# PDUv1.net
KiCad netlist of a schematic drawn in EAGLE
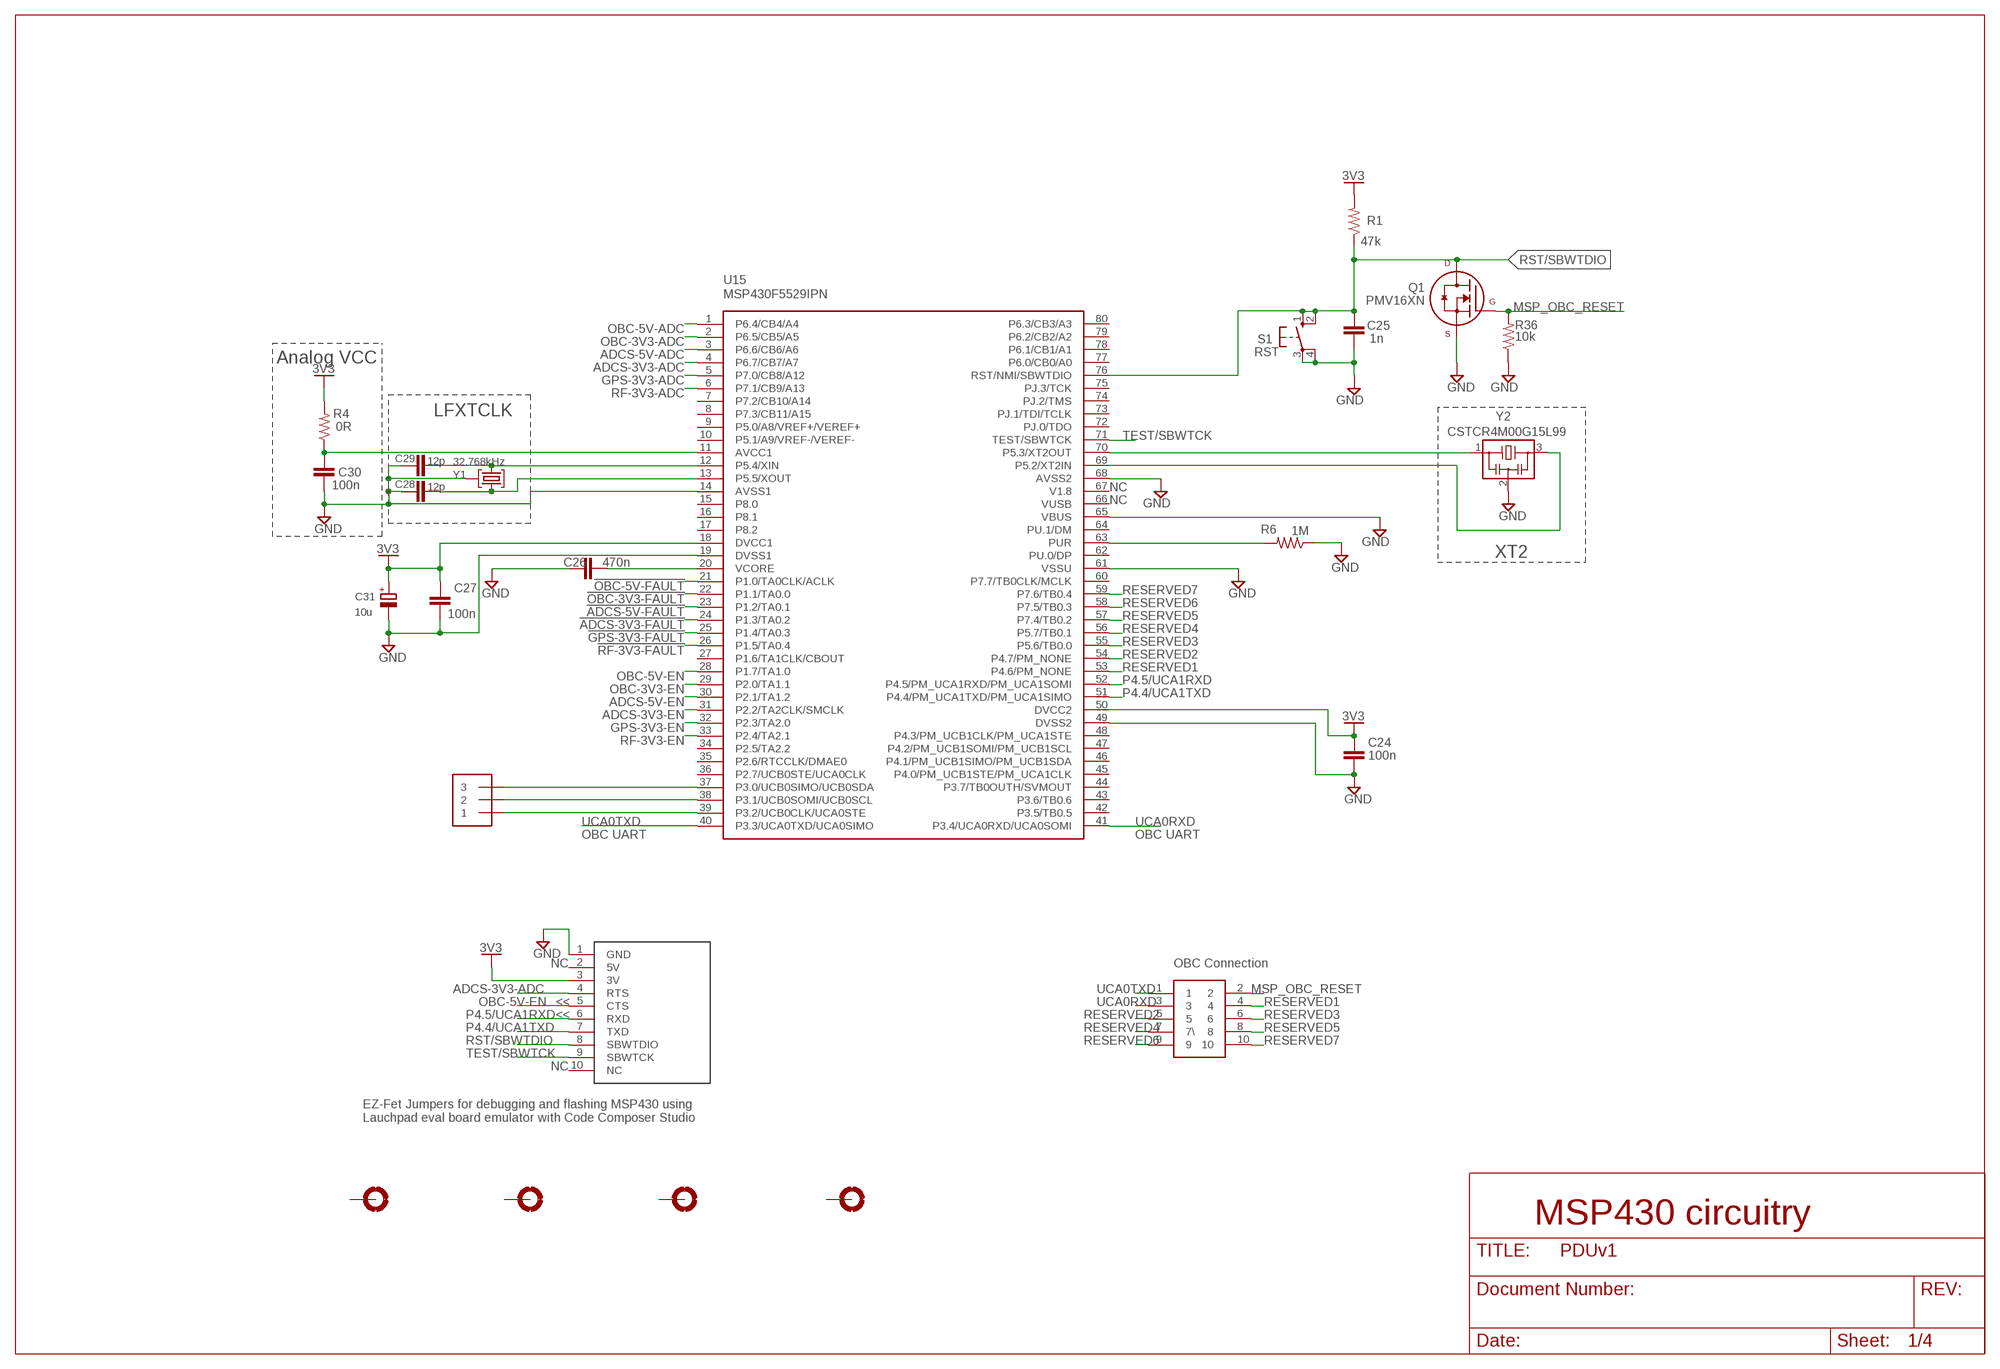
[diagram p0: schematic, sheet 1]
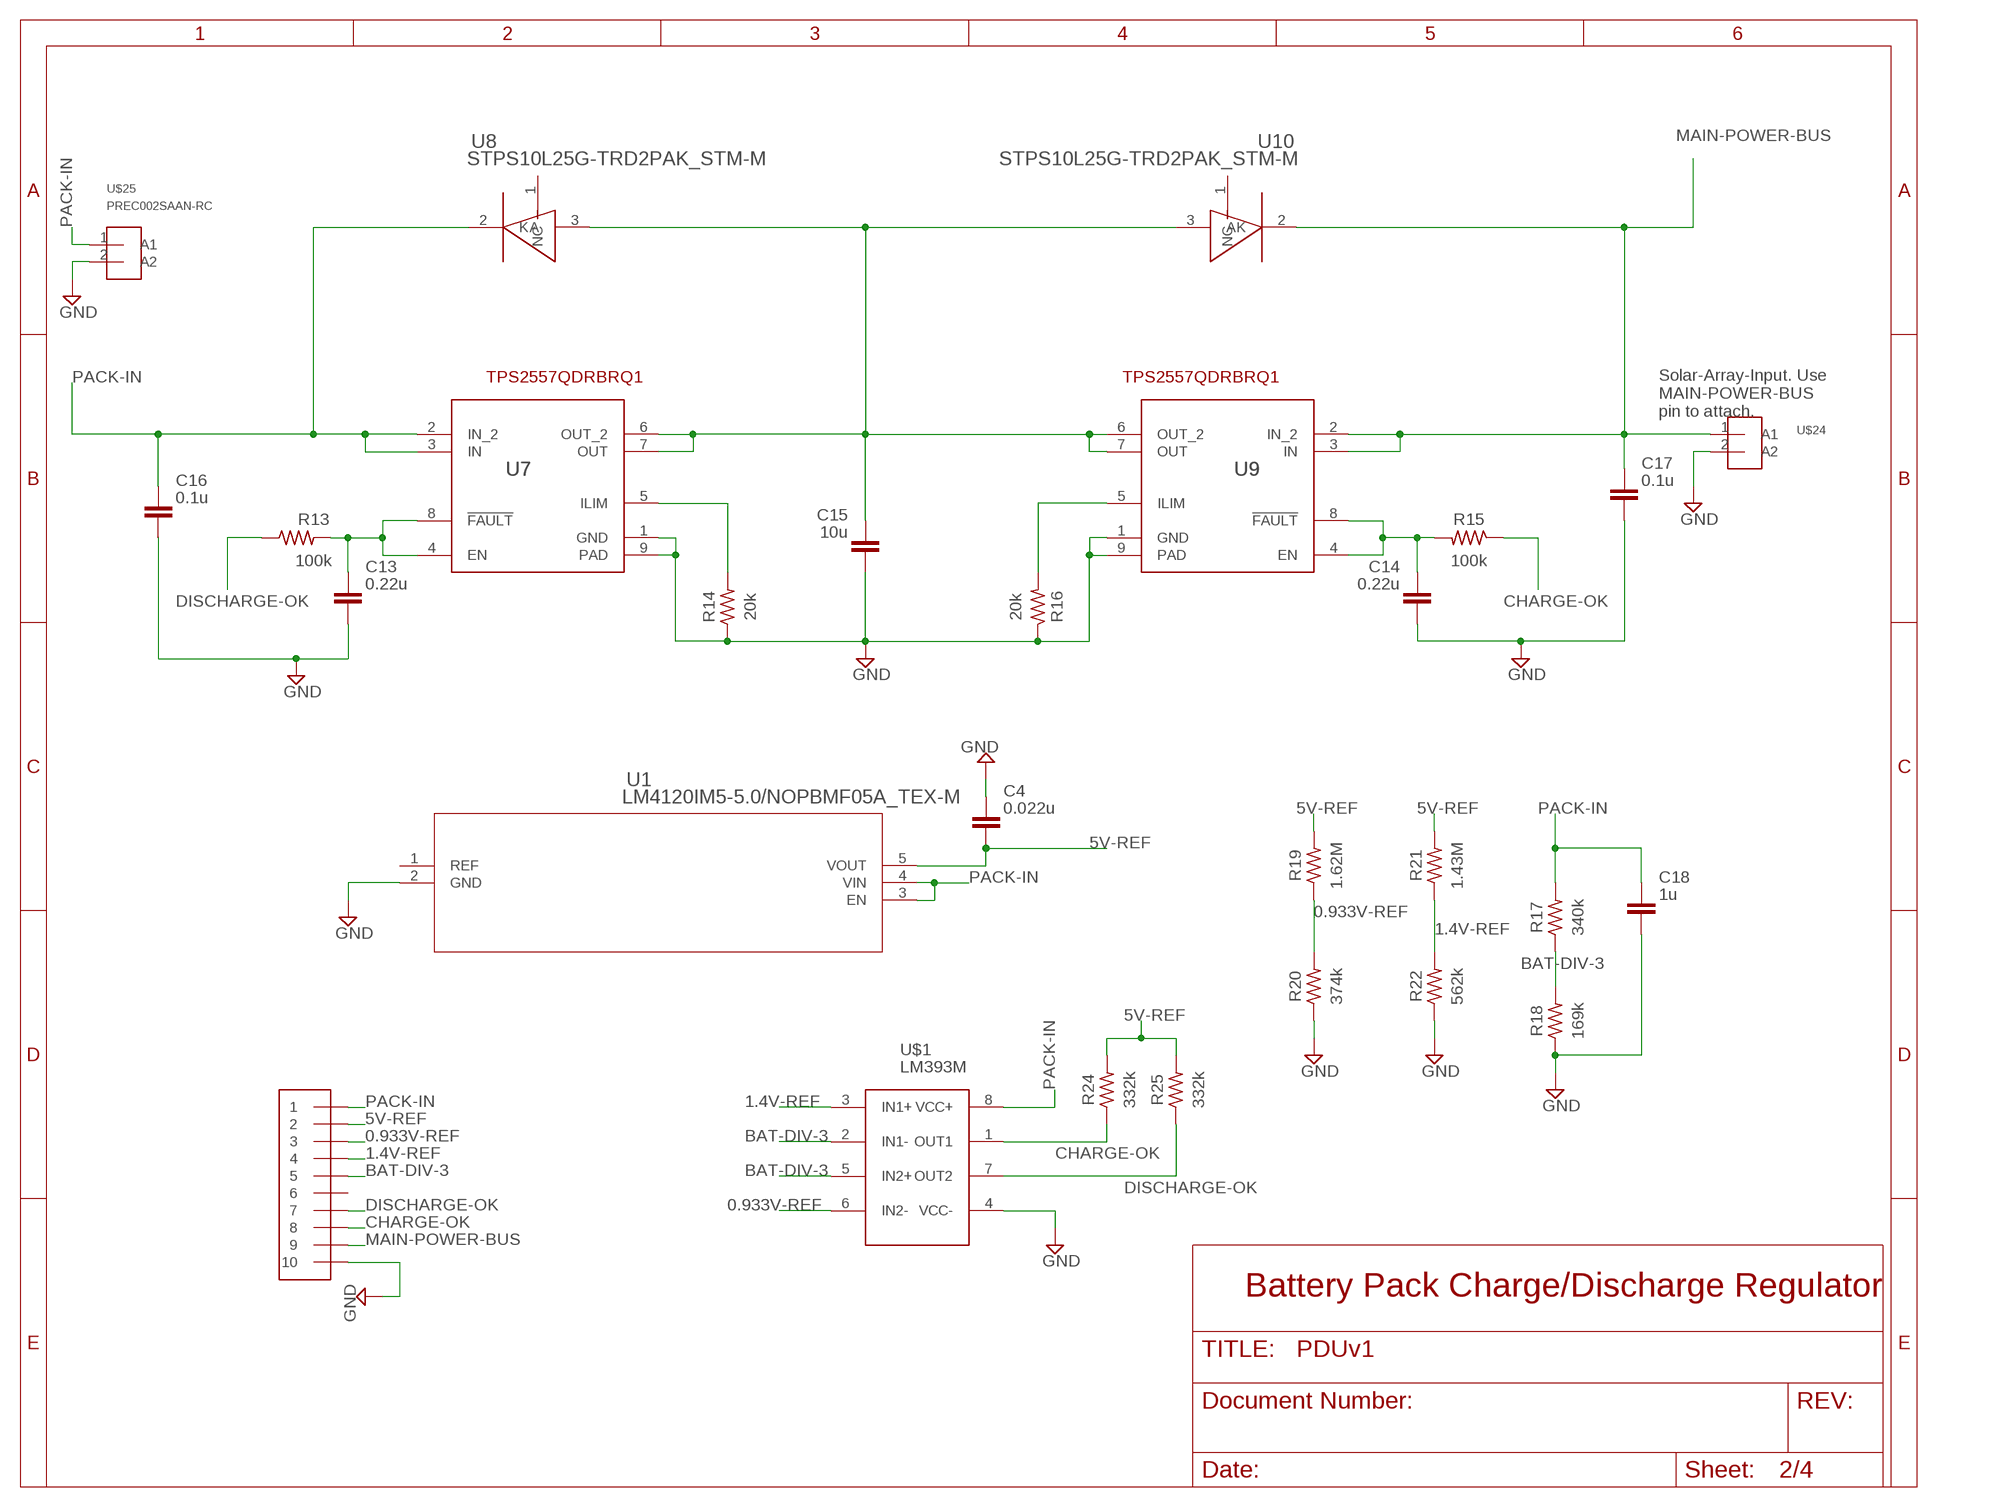
[diagram p1: schematic, sheet 2]
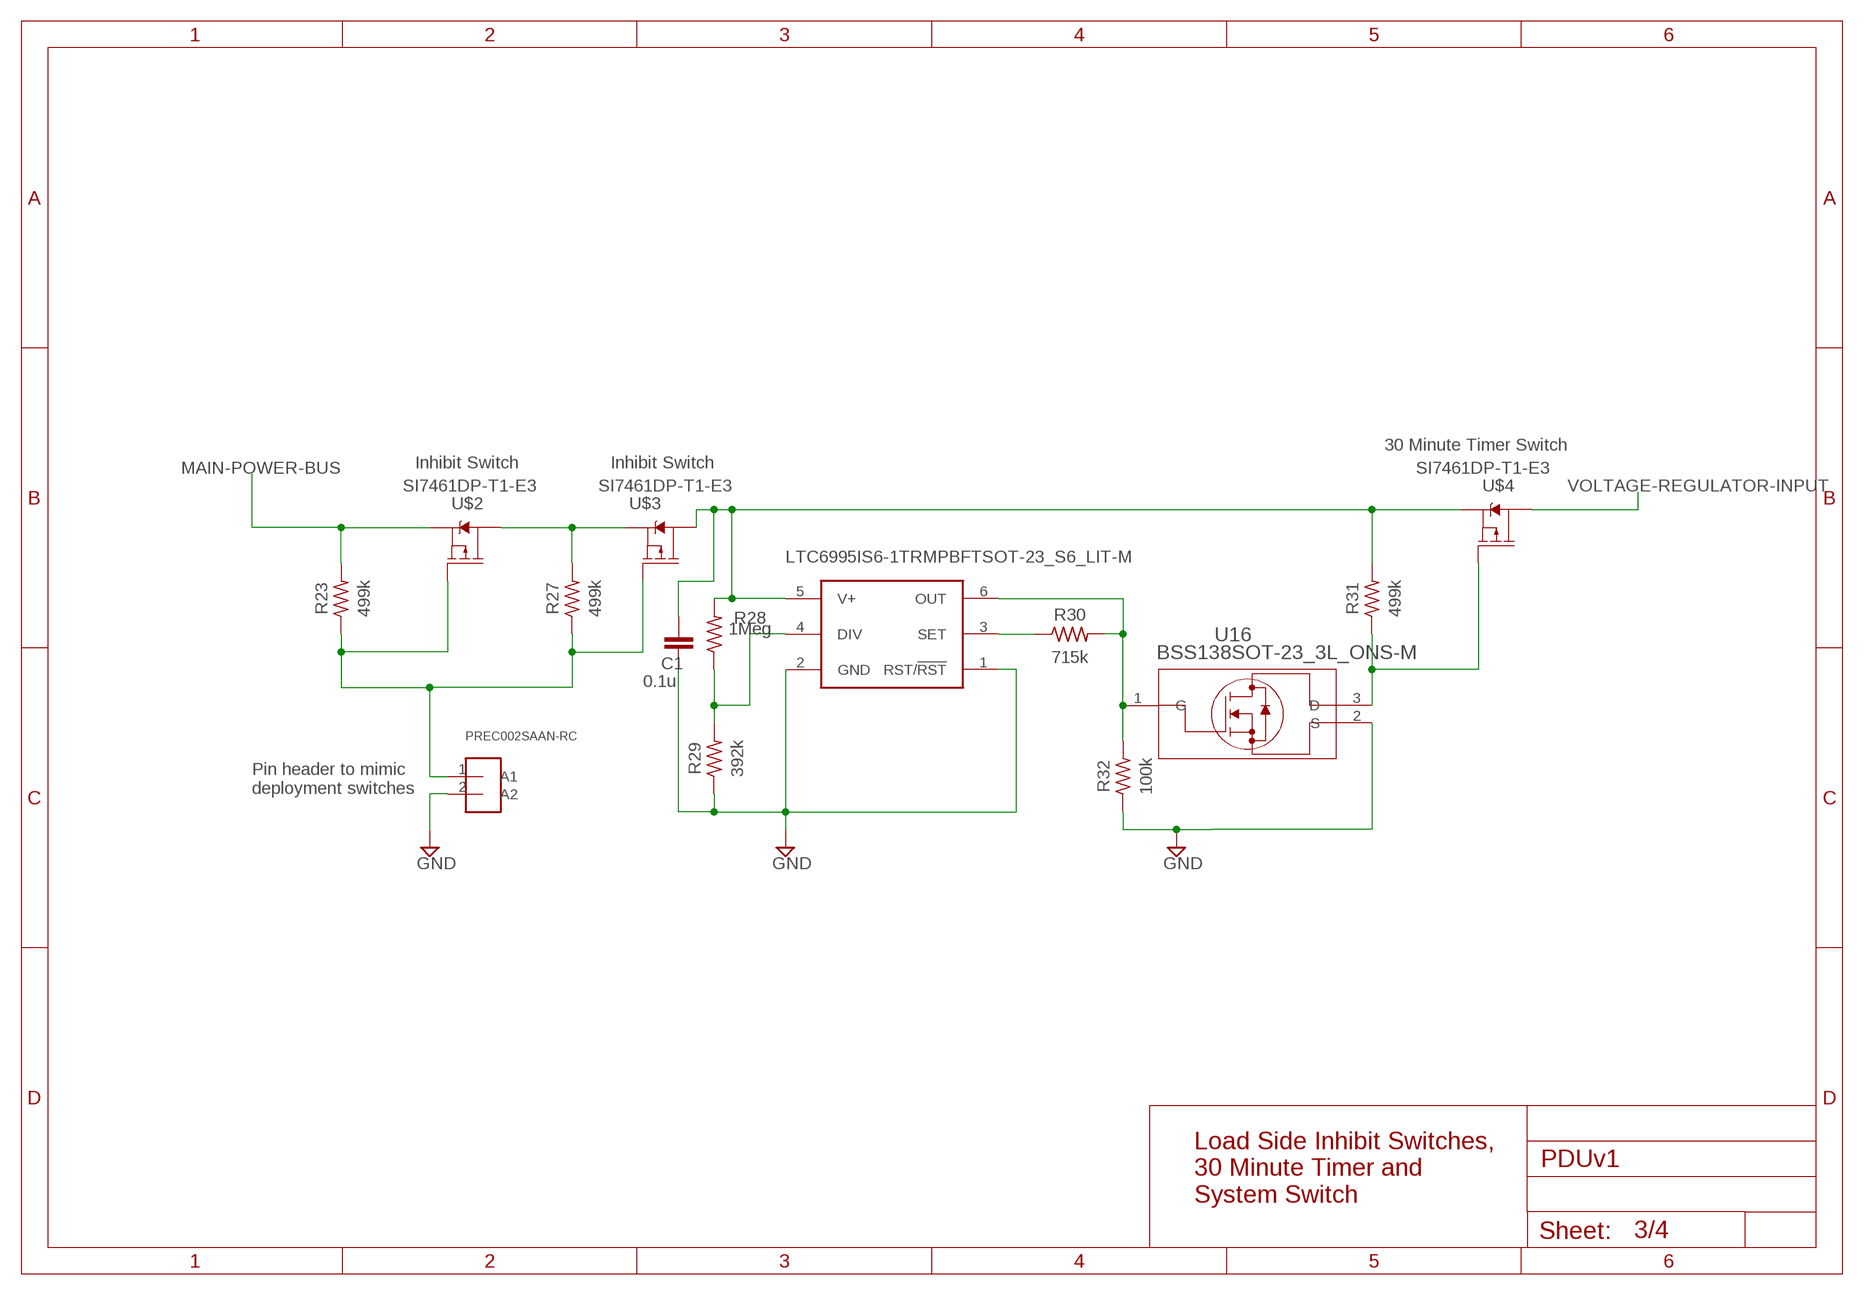
[diagram p2: schematic, sheet 3]
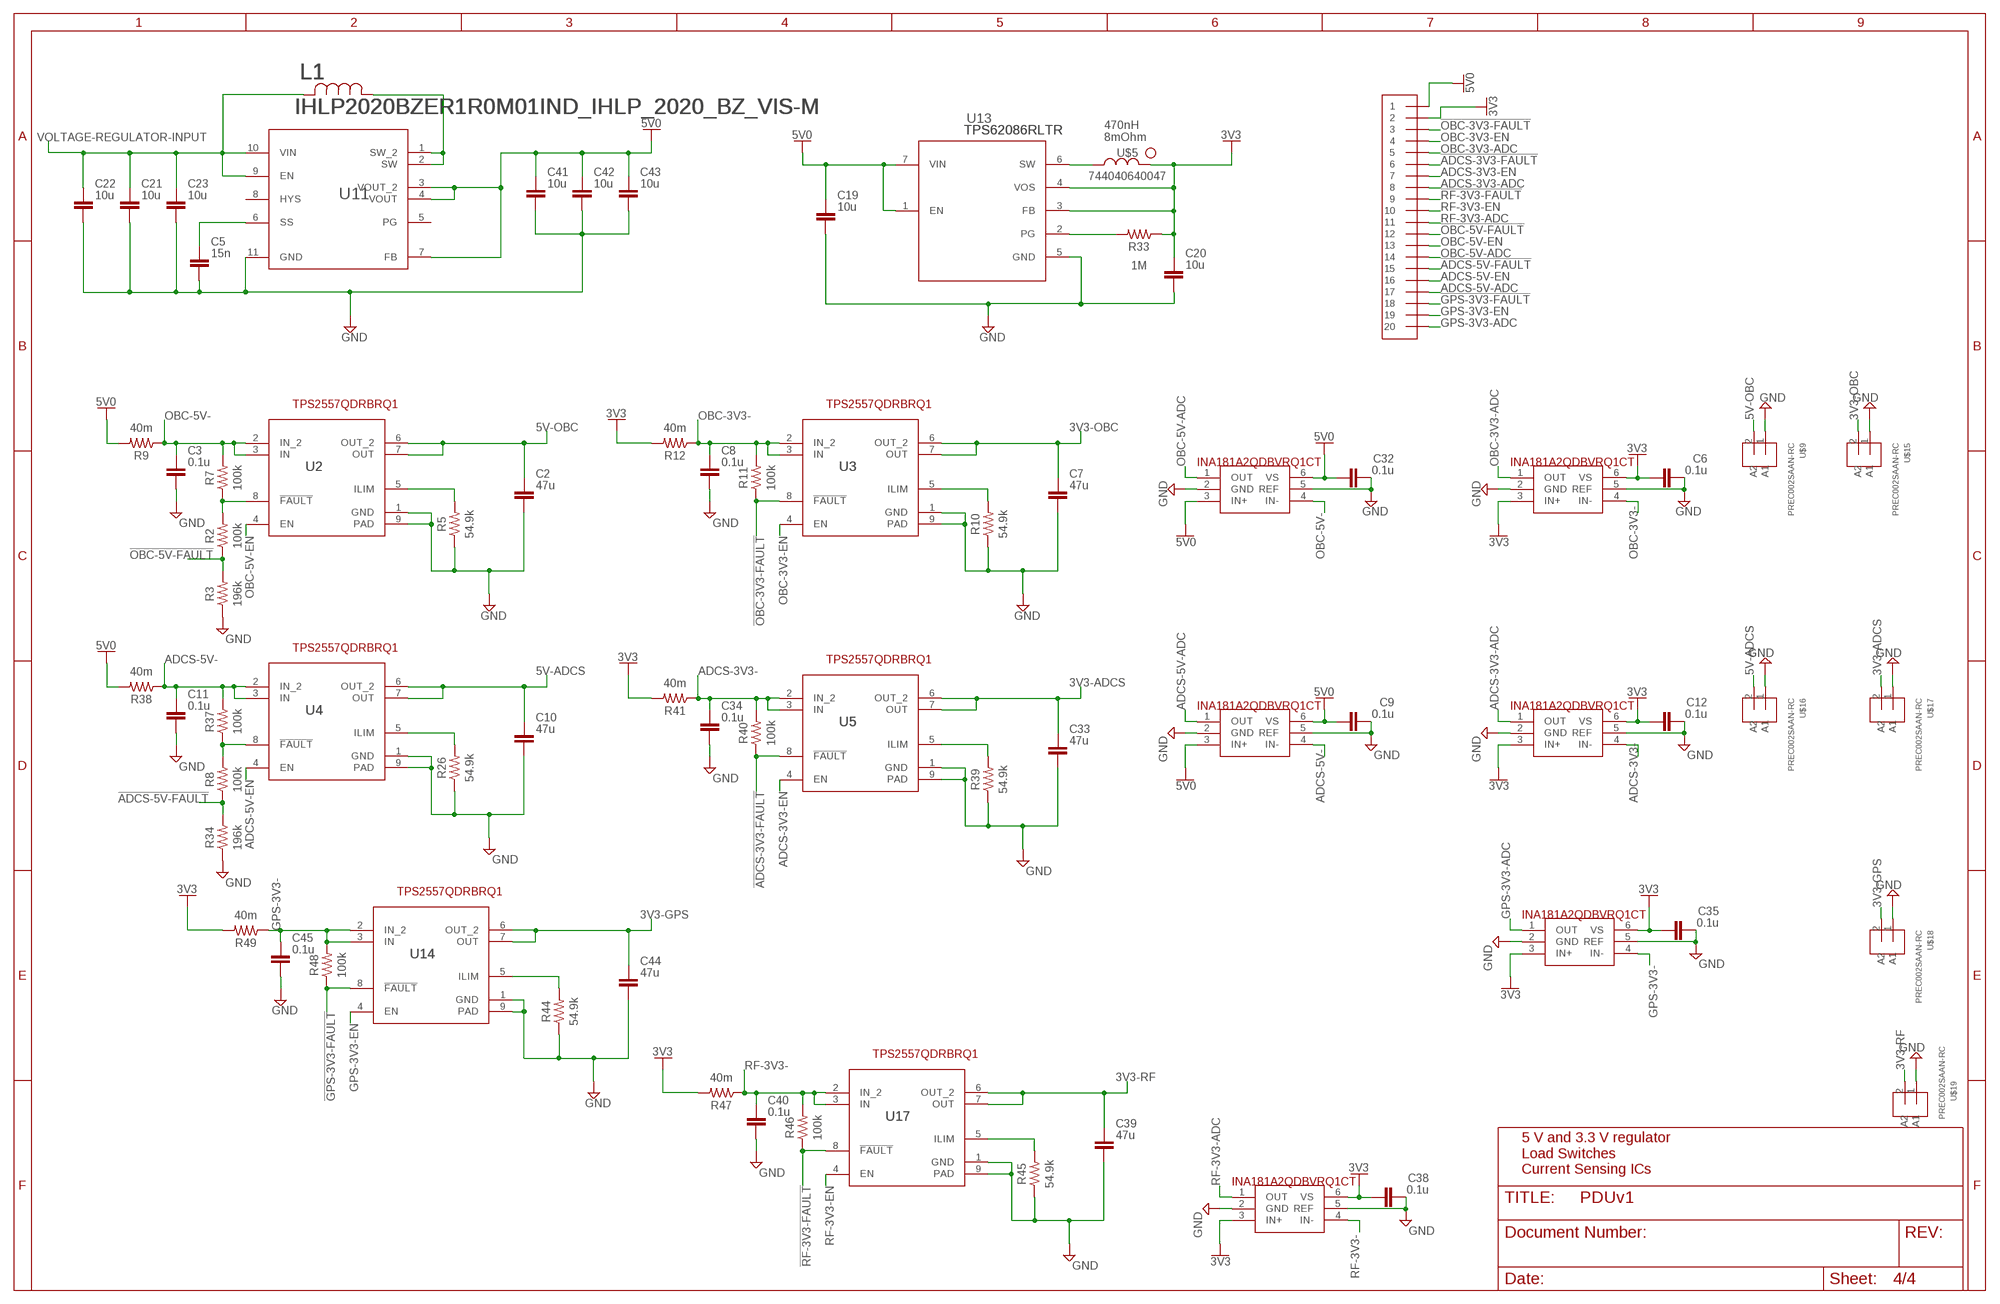
[diagram p3: schematic, sheet 4]

(export (version "E")
  (design (tool "Eeschema 10.0.6"))
  (components
    (comp (ref "C4")
      (value "0.022u")
      (footprint "eagle-import:CAPC1608X85")
      (libsource (lib "eagle-import") (part "CCHIP-0603(1608-METRIC)_"))
    )
    (comp (ref "C13")
      (value "0.22u")
      (footprint "eagle-import:CAPC1608X85")
      (libsource (lib "eagle-import") (part "CCHIP-0603(1608-METRIC)_"))
    )
    (comp (ref "C14")
      (value "0.22u")
      (footprint "eagle-import:CAPC1608X85")
      (libsource (lib "eagle-import") (part "CCHIP-0603(1608-METRIC)_"))
    )
    (comp (ref "C15")
      (value "10u")
      (footprint "eagle-import:CAPC1608X85")
      (libsource (lib "eagle-import") (part "CCHIP-0603(1608-METRIC)_"))
    )
    (comp (ref "C16")
      (value "0.1u")
      (footprint "eagle-import:CAPC1608X85")
      (libsource (lib "eagle-import") (part "CCHIP-0603(1608-METRIC)_"))
    )
    (comp (ref "C17")
      (value "0.1u")
      (footprint "eagle-import:CAPC1608X85")
      (libsource (lib "eagle-import") (part "CCHIP-0603(1608-METRIC)_"))
    )
    (comp (ref "C18")
      (value "1u")
      (footprint "eagle-import:CAPC1608X85")
      (libsource (lib "eagle-import") (part "CCHIP-0603(1608-METRIC)_"))
    )
    (comp (ref "R13")
      (value "100k")
      (footprint "eagle-import:RESC1608X60")
      (libsource (lib "eagle-import") (part "R-USCHIP-0603(1608-METRIC)_"))
    )
    (comp (ref "R14")
      (value "20k")
      (footprint "eagle-import:RESC1608X60")
      (libsource (lib "eagle-import") (part "R-USCHIP-0603(1608-METRIC)_"))
    )
    (comp (ref "R15")
      (value "100k")
      (footprint "eagle-import:RESC1608X60")
      (libsource (lib "eagle-import") (part "R-USCHIP-0603(1608-METRIC)_"))
    )
    (comp (ref "R16")
      (value "20k")
      (footprint "eagle-import:RESC1608X60")
      (libsource (lib "eagle-import") (part "R-USCHIP-0603(1608-METRIC)_"))
    )
    (comp (ref "R17")
      (value "340k")
      (footprint "eagle-import:RESC1608X60")
      (libsource (lib "eagle-import") (part "R-USCHIP-0603(1608-METRIC)_"))
    )
    (comp (ref "R18")
      (value "169k")
      (footprint "eagle-import:RESC1608X60")
      (libsource (lib "eagle-import") (part "R-USCHIP-0603(1608-METRIC)_"))
    )
    (comp (ref "R19")
      (value "1.62M")
      (footprint "eagle-import:RESC1608X60")
      (libsource (lib "eagle-import") (part "R-USCHIP-0603(1608-METRIC)_"))
    )
    (comp (ref "R20")
      (value "374k")
      (footprint "eagle-import:RESC1608X60")
      (libsource (lib "eagle-import") (part "R-USCHIP-0603(1608-METRIC)_"))
    )
    (comp (ref "R21")
      (value "1.43M")
      (footprint "eagle-import:RESC1608X60")
      (libsource (lib "eagle-import") (part "R-USCHIP-0603(1608-METRIC)_"))
    )
    (comp (ref "R22")
      (value "562k")
      (footprint "eagle-import:RESC1608X60")
      (libsource (lib "eagle-import") (part "R-USCHIP-0603(1608-METRIC)_"))
    )
    (comp (ref "R24")
      (value "332k")
      (footprint "eagle-import:RESC1608X60")
      (libsource (lib "eagle-import") (part "R-USCHIP-0603(1608-METRIC)_"))
    )
    (comp (ref "R25")
      (value "332k")
      (footprint "eagle-import:RESC1608X60")
      (libsource (lib "eagle-import") (part "R-USCHIP-0603(1608-METRIC)_"))
    )
    (comp (ref "U$1")
      (value "LM393M")
      (footprint "eagle-import:M08A-M")
      (libsource (lib "eagle-import") (part "LM393M"))
    )
    (comp (ref "U$20")
      (value "GRPB052VWQS-RC")
      (footprint "eagle-import:GRPB052VWQS-RC")
      (libsource (lib "eagle-import") (part "GRPB052VWQS-RC"))
    )
    (comp (ref "U$24")
      (value "PREC002SAAN-RC")
      (footprint "eagle-import:PREC002SAAN-RC")
      (libsource (lib "eagle-import") (part "PREC002SAAN-RC"))
    )
    (comp (ref "U$25")
      (value "PREC002SAAN-RC")
      (footprint "eagle-import:PREC002SAAN-RC")
      (libsource (lib "eagle-import") (part "PREC002SAAN-RC"))
    )
    (comp (ref "U1")
      (value "LM4120IM5-5.0/NOPBMF05A_TEX-M")
      (footprint "eagle-import:MF05A_TEX-M")
      (fields
        (field (name "MANUFACTURER_PART_NUMBER") "LM4120IM5-5.0/NOPB")
        (field (name "COPYRIGHT") "Copyright (C) 2018 Accelerated Designs. All rights reserved")
      )
      (libsource (lib "eagle-import") (part "LM4120IM5-5.0/NOPBMF05A_TEX-M"))
    )
    (comp (ref "U7")
      (value "Value")
      (footprint "eagle-import:DRB0008B")
      (fields (field (name "PARTNUMBER") "TPS2557QDRBRQ1") (field (name "MANUFACTURER") "Texas Instruments"))
      (libsource (lib "eagle-import") (part "TPS2557QDRBRQ1"))
    )
    (comp (ref "U8")
      (value "STPS10L25G-TRD2PAK_STM-M")
      (footprint "eagle-import:D2PAK_STM-M")
      (fields (field (name "MANUFACTURER_PART_NUMBER") "STPS10L25G-TR"))
      (libsource (lib "eagle-import") (part "STPS10L25G-TRD2PAK_STM-M"))
    )
    (comp (ref "U9")
      (value "Value")
      (footprint "eagle-import:DRB0008B")
      (fields (field (name "PARTNUMBER") "TPS2557QDRBRQ1") (field (name "MANUFACTURER") "Texas Instruments"))
      (libsource (lib "eagle-import") (part "TPS2557QDRBRQ1"))
    )
    (comp (ref "U10")
      (value "STPS10L25G-TRD2PAK_STM-M")
      (footprint "eagle-import:D2PAK_STM-M")
      (fields (field (name "MANUFACTURER_PART_NUMBER") "STPS10L25G-TR"))
      (libsource (lib "eagle-import") (part "STPS10L25G-TRD2PAK_STM-M"))
    )
    (comp (ref "C2")
      (value "47u")
      (footprint "eagle-import:CAPC1608X85")
      (libsource (lib "eagle-import") (part "CCHIP-0603(1608-METRIC)_"))
    )
    (comp (ref "C3")
      (value "0.1u")
      (footprint "eagle-import:CAPC1608X85")
      (libsource (lib "eagle-import") (part "CCHIP-0603(1608-METRIC)_"))
    )
    (comp (ref "C5")
      (value "15n")
      (footprint "eagle-import:CAPC1608X85")
      (libsource (lib "eagle-import") (part "CCHIP-0603(1608-METRIC)_"))
    )
    (comp (ref "C6")
      (value "0.1u")
      (footprint "eagle-import:CAPC1608X85")
      (libsource (lib "eagle-import") (part "CCHIP-0603(1608-METRIC)_"))
    )
    (comp (ref "C7")
      (value "47u")
      (footprint "eagle-import:CAPC1608X85")
      (libsource (lib "eagle-import") (part "CCHIP-0603(1608-METRIC)_"))
    )
    (comp (ref "C8")
      (value "0.1u")
      (footprint "eagle-import:CAPC1608X85")
      (libsource (lib "eagle-import") (part "CCHIP-0603(1608-METRIC)_"))
    )
    (comp (ref "C9")
      (value "0.1u")
      (footprint "eagle-import:CAPC1608X85")
      (libsource (lib "eagle-import") (part "CCHIP-0603(1608-METRIC)_"))
    )
    (comp (ref "C10")
      (value "47u")
      (footprint "eagle-import:CAPC1608X85")
      (libsource (lib "eagle-import") (part "CCHIP-0603(1608-METRIC)_"))
    )
    (comp (ref "C11")
      (value "0.1u")
      (footprint "eagle-import:CAPC1608X85")
      (libsource (lib "eagle-import") (part "CCHIP-0603(1608-METRIC)_"))
    )
    (comp (ref "C12")
      (value "0.1u")
      (footprint "eagle-import:CAPC1608X85")
      (libsource (lib "eagle-import") (part "CCHIP-0603(1608-METRIC)_"))
    )
    (comp (ref "C19")
      (value "10u")
      (footprint "eagle-import:CAPC1608X85")
      (libsource (lib "eagle-import") (part "CCHIP-0603(1608-METRIC)_"))
    )
    (comp (ref "C20")
      (value "10u")
      (footprint "eagle-import:CAPC1608X85")
      (libsource (lib "eagle-import") (part "CCHIP-0603(1608-METRIC)_"))
    )
    (comp (ref "C21")
      (value "10u")
      (footprint "eagle-import:CAPC1608X85")
      (libsource (lib "eagle-import") (part "CCHIP-0603(1608-METRIC)_"))
    )
    (comp (ref "C22")
      (value "10u")
      (footprint "eagle-import:CAPC1608X85")
      (libsource (lib "eagle-import") (part "CCHIP-0603(1608-METRIC)_"))
    )
    (comp (ref "C23")
      (value "10u")
      (footprint "eagle-import:CAPC1608X85")
      (libsource (lib "eagle-import") (part "CCHIP-0603(1608-METRIC)_"))
    )
    (comp (ref "C32")
      (value "0.1u")
      (footprint "eagle-import:CAPC1608X85")
      (libsource (lib "eagle-import") (part "CCHIP-0603(1608-METRIC)_"))
    )
    (comp (ref "C33")
      (value "47u")
      (footprint "eagle-import:CAPC1608X85")
      (libsource (lib "eagle-import") (part "CCHIP-0603(1608-METRIC)_"))
    )
    (comp (ref "C34")
      (value "0.1u")
      (footprint "eagle-import:CAPC1608X85")
      (libsource (lib "eagle-import") (part "CCHIP-0603(1608-METRIC)_"))
    )
    (comp (ref "C35")
      (value "0.1u")
      (footprint "eagle-import:CAPC1608X85")
      (libsource (lib "eagle-import") (part "CCHIP-0603(1608-METRIC)_"))
    )
    (comp (ref "C38")
      (value "0.1u")
      (footprint "eagle-import:CAPC1608X85")
      (libsource (lib "eagle-import") (part "CCHIP-0603(1608-METRIC)_"))
    )
    (comp (ref "C39")
      (value "47u")
      (footprint "eagle-import:CAPC1608X85")
      (libsource (lib "eagle-import") (part "CCHIP-0603(1608-METRIC)_"))
    )
    (comp (ref "C40")
      (value "0.1u")
      (footprint "eagle-import:CAPC1608X85")
      (libsource (lib "eagle-import") (part "CCHIP-0603(1608-METRIC)_"))
    )
    (comp (ref "C41")
      (value "10u")
      (footprint "eagle-import:CAPC1608X85")
      (libsource (lib "eagle-import") (part "CCHIP-0603(1608-METRIC)_"))
    )
    (comp (ref "C42")
      (value "10u")
      (footprint "eagle-import:CAPC1608X85")
      (libsource (lib "eagle-import") (part "CCHIP-0603(1608-METRIC)_"))
    )
    (comp (ref "C43")
      (value "10u")
      (footprint "eagle-import:CAPC1608X85")
      (libsource (lib "eagle-import") (part "CCHIP-0603(1608-METRIC)_"))
    )
    (comp (ref "C44")
      (value "47u")
      (footprint "eagle-import:CAPC1608X85")
      (libsource (lib "eagle-import") (part "CCHIP-0603(1608-METRIC)_"))
    )
    (comp (ref "C45")
      (value "0.1u")
      (footprint "eagle-import:CAPC1608X85")
      (libsource (lib "eagle-import") (part "CCHIP-0603(1608-METRIC)_"))
    )
    (comp (ref "L1")
      (value "IHLP2020BZER1R0M01IND_IHLP_2020_BZ_VIS-M")
      (footprint "eagle-import:IND_IHLP_2020_BZ_VIS-M")
      (fields (field (name "MANUFACTURER_PART_NUMBER") "IHLP2020BZER1R0M01"))
      (libsource (lib "eagle-import") (part "IHLP2020BZER1R0M01IND_IHLP_2020_BZ_VIS-M"))
    )
    (comp (ref "R2")
      (value "100k")
      (footprint "eagle-import:RESC1608X60")
      (libsource (lib "eagle-import") (part "R-USCHIP-0603(1608-METRIC)_"))
    )
    (comp (ref "R3")
      (value "196k")
      (footprint "eagle-import:RESC1608X60")
      (libsource (lib "eagle-import") (part "R-USCHIP-0603(1608-METRIC)_"))
    )
    (comp (ref "R5")
      (value "54.9k")
      (footprint "eagle-import:RESC1608X60")
      (libsource (lib "eagle-import") (part "R-USCHIP-0603(1608-METRIC)_"))
    )
    (comp (ref "R7")
      (value "100k")
      (footprint "eagle-import:RESC1608X60")
      (libsource (lib "eagle-import") (part "R-USCHIP-0603(1608-METRIC)_"))
    )
    (comp (ref "R8")
      (value "100k")
      (footprint "eagle-import:RESC1608X60")
      (libsource (lib "eagle-import") (part "R-USCHIP-0603(1608-METRIC)_"))
    )
    (comp (ref "R9")
      (value "40m")
      (footprint "eagle-import:RESC1608X60")
      (libsource (lib "eagle-import") (part "R-USCHIP-0603(1608-METRIC)_"))
    )
    (comp (ref "R10")
      (value "54.9k")
      (footprint "eagle-import:RESC1608X60")
      (libsource (lib "eagle-import") (part "R-USCHIP-0603(1608-METRIC)_"))
    )
    (comp (ref "R11")
      (value "100k")
      (footprint "eagle-import:RESC1608X60")
      (libsource (lib "eagle-import") (part "R-USCHIP-0603(1608-METRIC)_"))
    )
    (comp (ref "R12")
      (value "40m")
      (footprint "eagle-import:RESC1608X60")
      (libsource (lib "eagle-import") (part "R-USCHIP-0603(1608-METRIC)_"))
    )
    (comp (ref "R26")
      (value "54.9k")
      (footprint "eagle-import:RESC1608X60")
      (libsource (lib "eagle-import") (part "R-USCHIP-0603(1608-METRIC)_"))
    )
    (comp (ref "R33")
      (value "1M")
      (footprint "eagle-import:RESC1608X60")
      (libsource (lib "eagle-import") (part "R-USCHIP-0603(1608-METRIC)_"))
    )
    (comp (ref "R34")
      (value "196k")
      (footprint "eagle-import:RESC1608X60")
      (libsource (lib "eagle-import") (part "R-USCHIP-0603(1608-METRIC)_"))
    )
    (comp (ref "R37")
      (value "100k")
      (footprint "eagle-import:RESC1608X60")
      (libsource (lib "eagle-import") (part "R-USCHIP-0603(1608-METRIC)_"))
    )
    (comp (ref "R38")
      (value "40m")
      (footprint "eagle-import:RESC1608X60")
      (libsource (lib "eagle-import") (part "R-USCHIP-0603(1608-METRIC)_"))
    )
    (comp (ref "R39")
      (value "54.9k")
      (footprint "eagle-import:RESC1608X60")
      (libsource (lib "eagle-import") (part "R-USCHIP-0603(1608-METRIC)_"))
    )
    (comp (ref "R40")
      (value "100k")
      (footprint "eagle-import:RESC1608X60")
      (libsource (lib "eagle-import") (part "R-USCHIP-0603(1608-METRIC)_"))
    )
    (comp (ref "R41")
      (value "40m")
      (footprint "eagle-import:RESC1608X60")
      (libsource (lib "eagle-import") (part "R-USCHIP-0603(1608-METRIC)_"))
    )
    (comp (ref "R44")
      (value "54.9k")
      (footprint "eagle-import:RESC1608X60")
      (libsource (lib "eagle-import") (part "R-USCHIP-0603(1608-METRIC)_"))
    )
    (comp (ref "R45")
      (value "54.9k")
      (footprint "eagle-import:RESC1608X60")
      (libsource (lib "eagle-import") (part "R-USCHIP-0603(1608-METRIC)_"))
    )
    (comp (ref "R46")
      (value "100k")
      (footprint "eagle-import:RESC1608X60")
      (libsource (lib "eagle-import") (part "R-USCHIP-0603(1608-METRIC)_"))
    )
    (comp (ref "R47")
      (value "40m")
      (footprint "eagle-import:RESC1608X60")
      (libsource (lib "eagle-import") (part "R-USCHIP-0603(1608-METRIC)_"))
    )
    (comp (ref "R48")
      (value "100k")
      (footprint "eagle-import:RESC1608X60")
      (libsource (lib "eagle-import") (part "R-USCHIP-0603(1608-METRIC)_"))
    )
    (comp (ref "R49")
      (value "40m")
      (footprint "eagle-import:RESC1608X60")
      (libsource (lib "eagle-import") (part "R-USCHIP-0603(1608-METRIC)_"))
    )
    (comp (ref "U$5")
      (value "744040640047")
      (footprint "eagle-import:744040640047")
      (libsource (lib "eagle-import") (part "744040640047"))
    )
    (comp (ref "U$8")
      (value "INA181A2QDBVRQ1CT")
      (footprint "eagle-import:TSOT-23_S6_LIT-M")
      (libsource (lib "eagle-import") (part "INA181A2QDBVRQ1C"))
    )
    (comp (ref "U$9")
      (value "PREC002SAAN-RC")
      (footprint "eagle-import:PREC002SAAN-RC")
      (libsource (lib "eagle-import") (part "PREC002SAAN-RC"))
    )
    (comp (ref "U$10")
      (value "INA181A2QDBVRQ1CT")
      (footprint "eagle-import:TSOT-23_S6_LIT-M")
      (libsource (lib "eagle-import") (part "INA181A2QDBVRQ1C"))
    )
    (comp (ref "U$11")
      (value "INA181A2QDBVRQ1CT")
      (footprint "eagle-import:TSOT-23_S6_LIT-M")
      (libsource (lib "eagle-import") (part "INA181A2QDBVRQ1C"))
    )
    (comp (ref "U$12")
      (value "INA181A2QDBVRQ1CT")
      (footprint "eagle-import:TSOT-23_S6_LIT-M")
      (libsource (lib "eagle-import") (part "INA181A2QDBVRQ1C"))
    )
    (comp (ref "U$13")
      (value "INA181A2QDBVRQ1CT")
      (footprint "eagle-import:TSOT-23_S6_LIT-M")
      (libsource (lib "eagle-import") (part "INA181A2QDBVRQ1C"))
    )
    (comp (ref "U$14")
      (value "INA181A2QDBVRQ1CT")
      (footprint "eagle-import:TSOT-23_S6_LIT-M")
      (libsource (lib "eagle-import") (part "INA181A2QDBVRQ1C"))
    )
    (comp (ref "U$15")
      (value "PREC002SAAN-RC")
      (footprint "eagle-import:PREC002SAAN-RC")
      (libsource (lib "eagle-import") (part "PREC002SAAN-RC"))
    )
    (comp (ref "U$16")
      (value "PREC002SAAN-RC")
      (footprint "eagle-import:PREC002SAAN-RC")
      (libsource (lib "eagle-import") (part "PREC002SAAN-RC"))
    )
    (comp (ref "U$17")
      (value "PREC002SAAN-RC")
      (footprint "eagle-import:PREC002SAAN-RC")
      (libsource (lib "eagle-import") (part "PREC002SAAN-RC"))
    )
    (comp (ref "U$18")
      (value "PREC002SAAN-RC")
      (footprint "eagle-import:PREC002SAAN-RC")
      (libsource (lib "eagle-import") (part "PREC002SAAN-RC"))
    )
    (comp (ref "U$19")
      (value "PREC002SAAN-RC")
      (footprint "eagle-import:PREC002SAAN-RC")
      (libsource (lib "eagle-import") (part "PREC002SAAN-RC"))
    )
    (comp (ref "U$21")
      (value "GRPB102VWQS-RC")
      (footprint "eagle-import:GRPB102VWQS-RC")
      (libsource (lib "eagle-import") (part "GRPB102VWQS-RC"))
    )
    (comp (ref "U2")
      (value "Value")
      (footprint "eagle-import:DRB0008B")
      (fields (field (name "PARTNUMBER") "TPS2557QDRBRQ1") (field (name "MANUFACTURER") "Texas Instruments"))
      (libsource (lib "eagle-import") (part "TPS2557QDRBRQ1"))
    )
    (comp (ref "U3")
      (value "Value")
      (footprint "eagle-import:DRB0008B")
      (fields (field (name "PARTNUMBER") "TPS2557QDRBRQ1") (field (name "MANUFACTURER") "Texas Instruments"))
      (libsource (lib "eagle-import") (part "TPS2557QDRBRQ1"))
    )
    (comp (ref "U4")
      (value "Value")
      (footprint "eagle-import:DRB0008B")
      (fields (field (name "PARTNUMBER") "TPS2557QDRBRQ1") (field (name "MANUFACTURER") "Texas Instruments"))
      (libsource (lib "eagle-import") (part "TPS2557QDRBRQ1"))
    )
    (comp (ref "U5")
      (value "Value")
      (footprint "eagle-import:DRB0008B")
      (fields (field (name "PARTNUMBER") "TPS2557QDRBRQ1") (field (name "MANUFACTURER") "Texas Instruments"))
      (libsource (lib "eagle-import") (part "TPS2557QDRBRQ1"))
    )
    (comp (ref "U11")
      (value "TPS61232DRCT")
      (footprint "eagle-import:DRC0010G")
      (fields
        (field (name "MANUFACTURER") "Texas Instruments")
        (field (name "PARTNUMBER") "TPS61232DRC")
        (field (name "APPROVEDBY") "Not shown in title block")
        (field (name "AUTHOR") "Not shown in title block")
        (field (name "CHECKEDBY") "Not shown in title block")
        (field (name "ENGINEER") "Not shown in title block")
        (field (name "MODIFIEDDATE") "Not shown in title block")
        (field (name "PUBLISHER") "Texas Instruments")
        (field (name "SYMBOLCREATOR") "a0411947")
      )
      (libsource (lib "eagle-import") (part "TPS61232DRCT"))
    )
    (comp (ref "U13")
      (value "TPS62086RLTR")
      (footprint "eagle-import:RLT0007A")
      (fields (field (name "MANUFACTURER") "Texas Instruments"))
      (libsource (lib "eagle-import") (part "TPS62086RLTR"))
    )
    (comp (ref "U14")
      (value "Value")
      (footprint "eagle-import:DRB0008B")
      (fields (field (name "PARTNUMBER") "TPS2557QDRBRQ1") (field (name "MANUFACTURER") "Texas Instruments"))
      (libsource (lib "eagle-import") (part "TPS2557QDRBRQ1"))
    )
    (comp (ref "U17")
      (value "Value")
      (footprint "eagle-import:DRB0008B")
      (fields (field (name "PARTNUMBER") "TPS2557QDRBRQ1") (field (name "MANUFACTURER") "Texas Instruments"))
      (libsource (lib "eagle-import") (part "TPS2557QDRBRQ1"))
    )
    (comp (ref "C1")
      (value "0.1u")
      (footprint "eagle-import:CAPC1608X85")
      (libsource (lib "eagle-import") (part "CCHIP-0603(1608-METRIC)_"))
    )
    (comp (ref "R23")
      (value "499k")
      (footprint "eagle-import:RESC1608X60")
      (libsource (lib "eagle-import") (part "R-USCHIP-0603(1608-METRIC)_"))
    )
    (comp (ref "R27")
      (value "499k")
      (footprint "eagle-import:RESC1608X60")
      (libsource (lib "eagle-import") (part "R-USCHIP-0603(1608-METRIC)_"))
    )
    (comp (ref "R28")
      (value "1Meg")
      (footprint "eagle-import:RESC1608X60")
      (libsource (lib "eagle-import") (part "R-USCHIP-0603(1608-METRIC)_"))
    )
    (comp (ref "R29")
      (value "392k")
      (footprint "eagle-import:RESC1608X60")
      (libsource (lib "eagle-import") (part "R-USCHIP-0603(1608-METRIC)_"))
    )
    (comp (ref "R30")
      (value "715k")
      (footprint "eagle-import:RESC1608X60")
      (libsource (lib "eagle-import") (part "R-USCHIP-0603(1608-METRIC)_"))
    )
    (comp (ref "R31")
      (value "499k")
      (footprint "eagle-import:RESC1608X60")
      (libsource (lib "eagle-import") (part "R-USCHIP-0603(1608-METRIC)_"))
    )
    (comp (ref "R32")
      (value "100k")
      (footprint "eagle-import:RESC1608X60")
      (libsource (lib "eagle-import") (part "R-USCHIP-0603(1608-METRIC)_"))
    )
    (comp (ref "U$2")
      (value "SI7461DP-T1-E3")
      (footprint "eagle-import:MOSFET_65DP-T1-E3_VIS")
      (libsource (lib "eagle-import") (part "SI7461DP-T1-E3"))
    )
    (comp (ref "U$3")
      (value "SI7461DP-T1-E3")
      (footprint "eagle-import:MOSFET_65DP-T1-E3_VIS")
      (libsource (lib "eagle-import") (part "SI7461DP-T1-E3"))
    )
    (comp (ref "U$4")
      (value "SI7461DP-T1-E3")
      (footprint "eagle-import:MOSFET_65DP-T1-E3_VIS")
      (libsource (lib "eagle-import") (part "SI7461DP-T1-E3"))
    )
    (comp (ref "U$7")
      (value "PREC002SAAN-RC")
      (footprint "eagle-import:PREC002SAAN-RC")
      (libsource (lib "eagle-import") (part "PREC002SAAN-RC"))
    )
    (comp (ref "U12")
      (value "LTC6995IS6-1TRMPBFTSOT-23_S6_LIT-M")
      (footprint "eagle-import:TSOT-23_S6_LIT-M")
      (fields (field (name "MANUFACTURER_PART_NUMBER") "LTC6995IS6-1#TRMPBF"))
      (libsource (lib "eagle-import") (part "LTC6995IS6-1TRMPBFTSOT-23_S6_LIT-M"))
    )
    (comp (ref "U16")
      (value "BSS138SOT-23_3L_ONS-M")
      (footprint "eagle-import:SOT-23_3L_ONS-M")
      (fields
        (field (name "MANUFACTURER_PART_NUMBER") "BSS138")
        (field (name "COPYRIGHT") "Copyright (C) 2018 Accelerated Designs. All rights reserved")
      )
      (libsource (lib "eagle-import") (part "BSS138SOT-23_3L_ONS-M"))
    )
    (comp (ref "C24")
      (value "100n")
      (footprint "eagle-import:C0402")
      (libsource (lib "eagle-import") (part "C-EUC0402"))
    )
    (comp (ref "C25")
      (value "1n")
      (footprint "eagle-import:C0402")
      (libsource (lib "eagle-import") (part "C-EUC0402"))
    )
    (comp (ref "C26")
      (value "470n")
      (footprint "eagle-import:C0402")
      (libsource (lib "eagle-import") (part "C-EUC0402"))
    )
    (comp (ref "C27")
      (value "100n")
      (footprint "eagle-import:C0402")
      (libsource (lib "eagle-import") (part "C-EUC0402"))
    )
    (comp (ref "C28")
      (value "12p")
      (footprint "eagle-import:C0402")
      (libsource (lib "eagle-import") (part "C-EUC0402"))
    )
    (comp (ref "C29")
      (value "12p")
      (footprint "eagle-import:C0402")
      (libsource (lib "eagle-import") (part "C-EUC0402"))
    )
    (comp (ref "C30")
      (value "100n")
      (footprint "eagle-import:C0402")
      (libsource (lib "eagle-import") (part "C-EUC0402"))
    )
    (comp (ref "C31")
      (value "10u")
      (footprint "eagle-import:A_3216-18R")
      (libsource (lib "eagle-import") (part "POLARIZED_CAP"))
    )
    (comp (ref "J5")
      (value "HDR_10_EZFET_DEBUGGER")
      (footprint "eagle-import:HDRV10W66P254_10X1_2540X254H858")
      (libsource (lib "eagle-import") (part "HDR_10_EZFET_DEBUGGER"))
    )
    (comp (ref "MH1")
      (value "MTGP700H400")
      (footprint "eagle-import:MTGP700H400")
      (libsource (lib "eagle-import") (part "MTGP700H400"))
    )
    (comp (ref "MH2")
      (value "MTGP700H400")
      (footprint "eagle-import:MTGP700H400")
      (libsource (lib "eagle-import") (part "MTGP700H400"))
    )
    (comp (ref "MH3")
      (value "MTGP700H400")
      (footprint "eagle-import:MTGP700H400")
      (libsource (lib "eagle-import") (part "MTGP700H400"))
    )
    (comp (ref "MH4")
      (value "MTGP700H400")
      (footprint "eagle-import:MTGP700H400")
      (libsource (lib "eagle-import") (part "MTGP700H400"))
    )
    (comp (ref "Q1")
      (value "PMV16XN")
      (footprint "eagle-import:SOT23-3P95_230X110L20X43N_PMV16XN")
      (libsource (lib "eagle-import") (part "PMV16XN"))
    )
    (comp (ref "R1")
      (value "47k")
      (footprint "eagle-import:R0402")
      (libsource (lib "eagle-import") (part "R-US_R0402"))
    )
    (comp (ref "R4")
      (value "0R")
      (footprint "eagle-import:R0402")
      (libsource (lib "eagle-import") (part "R-US_R0402"))
    )
    (comp (ref "R6")
      (value "1M")
      (footprint "eagle-import:R0603")
      (libsource (lib "eagle-import") (part "R-US_R0603"))
    )
    (comp (ref "R36")
      (value "10k")
      (footprint "eagle-import:R0603")
      (libsource (lib "eagle-import") (part "R-US_R0603"))
    )
    (comp (ref "S1")
      (value "RST")
      (footprint "eagle-import:B3F-10XX")
      (fields (field (name "MPN") "B3F-1000"))
      (libsource (lib "eagle-import") (part "10-XX"))
    )
    (comp (ref "U$22")
      (value "OBC-CONNECTOR")
      (footprint "eagle-import:OBC-CON")
      (libsource (lib "eagle-import") (part "OBC-CONNECTOR"))
    )
    (comp (ref "U$23")
      (value "GRPB031VWTC-RC")
      (footprint "eagle-import:GRPB031VWTC-RC")
      (libsource (lib "eagle-import") (part "GRPB031VWTC-RC"))
    )
    (comp (ref "U15")
      (value "MSP430F5529IPN")
      (footprint "eagle-import:QFP80P50_1400X1400X160L60X22N")
      (libsource (lib "eagle-import") (part "MSP430F5529IPN"))
    )
    (comp (ref "Y1")
      (value "32.768kHz")
      (footprint "eagle-import:MS3V-T1R")
      (libsource (lib "eagle-import") (part "MS3V-T1R"))
    )
    (comp (ref "Y2")
      (value "CSTCR4M00G15L99")
      (footprint "eagle-import:MURATA-FILTER_CSTCR")
      (fields (field (name "MPN") "CSTCR6M00G53-R0"))
      (libsource (lib "eagle-import") (part "CSTCR4M00G15L996M00G53Z"))
    )
  )
  (nets
    (net (code "1") (name "0.933V-REF") (class "Default")
      (node (ref "R19") (pin "1") (pinfunction "1_1") (pintype "passive"))
      (node (ref "R20") (pin "2") (pinfunction "2_2") (pintype "passive"))
      (node (ref "U$1") (pin "6") (pinfunction "IN2-_6") (pintype "passive"))
      (node (ref "U$20") (pin "3") (pinfunction "3_3") (pintype "bidirectional"))
    )
    (net (code "2") (name "1.4V-REF") (class "Default")
      (node (ref "R21") (pin "1") (pinfunction "1_1") (pintype "passive"))
      (node (ref "R22") (pin "2") (pinfunction "2_2") (pintype "passive"))
      (node (ref "U$1") (pin "3") (pinfunction "IN1+_3") (pintype "passive"))
      (node (ref "U$20") (pin "4") (pinfunction "4_4") (pintype "bidirectional"))
    )
    (net (code "3") (name "3V3") (class "Default")
      (node (ref "C12") (pin "1") (pinfunction "1_1") (pintype "passive"))
      (node (ref "C20") (pin "1") (pinfunction "1_1") (pintype "passive"))
      (node (ref "C24") (pin "1") (pinfunction "1_1") (pintype "passive"))
      (node (ref "C27") (pin "2") (pinfunction "2_2") (pintype "passive"))
      (node (ref "C31") (pin "+") (pinfunction "+_+") (pintype "passive"))
      (node (ref "C35") (pin "1") (pinfunction "1_1") (pintype "passive"))
      (node (ref "C38") (pin "1") (pinfunction "1_1") (pintype "passive"))
      (node (ref "C6") (pin "1") (pinfunction "1_1") (pintype "passive"))
      (node (ref "J5") (pin "3") (pinfunction "3V_3") (pintype "bidirectional"))
      (node (ref "R1") (pin "2") (pinfunction "2_2") (pintype "passive"))
      (node (ref "R12") (pin "2") (pinfunction "2_2") (pintype "passive"))
      (node (ref "R33") (pin "1") (pinfunction "1_1") (pintype "passive"))
      (node (ref "R4") (pin "2") (pinfunction "2_2") (pintype "passive"))
      (node (ref "R41") (pin "2") (pinfunction "2_2") (pintype "passive"))
      (node (ref "R47") (pin "2") (pinfunction "2_2") (pintype "passive"))
      (node (ref "R49") (pin "2") (pinfunction "2_2") (pintype "passive"))
      (node (ref "U$10") (pin "3") (pinfunction "IN+_3") (pintype "bidirectional"))
      (node (ref "U$10") (pin "6") (pinfunction "VS_6") (pintype "bidirectional"))
      (node (ref "U$12") (pin "3") (pinfunction "IN+_3") (pintype "bidirectional"))
      (node (ref "U$12") (pin "6") (pinfunction "VS_6") (pintype "bidirectional"))
      (node (ref "U$13") (pin "3") (pinfunction "IN+_3") (pintype "bidirectional"))
      (node (ref "U$13") (pin "6") (pinfunction "VS_6") (pintype "bidirectional"))
      (node (ref "U$14") (pin "3") (pinfunction "IN+_3") (pintype "bidirectional"))
      (node (ref "U$14") (pin "6") (pinfunction "VS_6") (pintype "bidirectional"))
      (node (ref "U$21") (pin "2") (pinfunction "2_2") (pintype "bidirectional"))
      (node (ref "U$5") (pin "1") (pinfunction "DOT_1") (pintype "passive"))
      (node (ref "U13") (pin "3") (pinfunction "FB_3") (pintype "input"))
      (node (ref "U13") (pin "4") (pinfunction "VOS_4") (pintype "input"))
      (node (ref "U15") (pin "18") (pinfunction "DVCC1_18") (pintype "bidirectional"))
      (node (ref "U15") (pin "50") (pinfunction "DVCC2_50") (pintype "bidirectional"))
    )
    (net (code "4") (name "3V3-ADCS") (class "Default")
      (node (ref "C33") (pin "1") (pinfunction "1_1") (pintype "passive"))
      (node (ref "U$17") (pin "2") (pinfunction "A2_2") (pintype "bidirectional"))
      (node (ref "U5") (pin "6") (pinfunction "OUT_2_6") (pintype "power_in"))
      (node (ref "U5") (pin "7") (pinfunction "OUT_7") (pintype "power_in"))
    )
    (net (code "5") (name "3V3-GPS") (class "Default")
      (node (ref "C44") (pin "1") (pinfunction "1_1") (pintype "passive"))
      (node (ref "U$18") (pin "2") (pinfunction "A2_2") (pintype "bidirectional"))
      (node (ref "U14") (pin "6") (pinfunction "OUT_2_6") (pintype "power_in"))
      (node (ref "U14") (pin "7") (pinfunction "OUT_7") (pintype "power_in"))
    )
    (net (code "6") (name "3V3-OBC") (class "Default")
      (node (ref "C7") (pin "1") (pinfunction "1_1") (pintype "passive"))
      (node (ref "U$15") (pin "2") (pinfunction "A2_2") (pintype "bidirectional"))
      (node (ref "U3") (pin "6") (pinfunction "OUT_2_6") (pintype "power_in"))
      (node (ref "U3") (pin "7") (pinfunction "OUT_7") (pintype "power_in"))
    )
    (net (code "7") (name "3V3-RF") (class "Default")
      (node (ref "C39") (pin "1") (pinfunction "1_1") (pintype "passive"))
      (node (ref "U$19") (pin "2") (pinfunction "A2_2") (pintype "bidirectional"))
      (node (ref "U17") (pin "6") (pinfunction "OUT_2_6") (pintype "power_in"))
      (node (ref "U17") (pin "7") (pinfunction "OUT_7") (pintype "power_in"))
    )
    (net (code "8") (name "5V-ADCS") (class "Default")
      (node (ref "C10") (pin "1") (pinfunction "1_1") (pintype "passive"))
      (node (ref "U$16") (pin "2") (pinfunction "A2_2") (pintype "bidirectional"))
      (node (ref "U4") (pin "6") (pinfunction "OUT_2_6") (pintype "power_in"))
      (node (ref "U4") (pin "7") (pinfunction "OUT_7") (pintype "power_in"))
    )
    (net (code "9") (name "5V-OBC") (class "Default")
      (node (ref "C2") (pin "1") (pinfunction "1_1") (pintype "passive"))
      (node (ref "U$9") (pin "2") (pinfunction "A2_2") (pintype "bidirectional"))
      (node (ref "U2") (pin "6") (pinfunction "OUT_2_6") (pintype "power_in"))
      (node (ref "U2") (pin "7") (pinfunction "OUT_7") (pintype "power_in"))
    )
    (net (code "10") (name "5V-REF") (class "Default")
      (node (ref "C4") (pin "2") (pinfunction "2_2") (pintype "passive"))
      (node (ref "R19") (pin "2") (pinfunction "2_2") (pintype "passive"))
      (node (ref "R21") (pin "2") (pinfunction "2_2") (pintype "passive"))
      (node (ref "R24") (pin "2") (pinfunction "2_2") (pintype "passive"))
      (node (ref "R25") (pin "2") (pinfunction "2_2") (pintype "passive"))
      (node (ref "U$20") (pin "2") (pinfunction "2_2") (pintype "bidirectional"))
      (node (ref "U1") (pin "5") (pinfunction "VOUT_5") (pintype "output"))
    )
    (net (code "11") (name "5V0") (class "Default")
      (node (ref "C19") (pin "1") (pinfunction "1_1") (pintype "passive"))
      (node (ref "C32") (pin "1") (pinfunction "1_1") (pintype "passive"))
      (node (ref "C41") (pin "1") (pinfunction "1_1") (pintype "passive"))
      (node (ref "C42") (pin "1") (pinfunction "1_1") (pintype "passive"))
      (node (ref "C43") (pin "1") (pinfunction "1_1") (pintype "passive"))
      (node (ref "C9") (pin "1") (pinfunction "1_1") (pintype "passive"))
      (node (ref "R38") (pin "2") (pinfunction "2_2") (pintype "passive"))
      (node (ref "R9") (pin "2") (pinfunction "2_2") (pintype "passive"))
      (node (ref "U$11") (pin "3") (pinfunction "IN+_3") (pintype "bidirectional"))
      (node (ref "U$11") (pin "6") (pinfunction "VS_6") (pintype "bidirectional"))
      (node (ref "U$21") (pin "1") (pinfunction "1_1") (pintype "bidirectional"))
      (node (ref "U$8") (pin "3") (pinfunction "IN+_3") (pintype "bidirectional"))
      (node (ref "U$8") (pin "6") (pinfunction "VS_6") (pintype "bidirectional"))
      (node (ref "U11") (pin "3") (pinfunction "VOUT_2_3") (pintype "power_in"))
      (node (ref "U11") (pin "4") (pinfunction "VOUT_4") (pintype "power_in"))
      (node (ref "U11") (pin "7") (pinfunction "FB_7") (pintype "input"))
      (node (ref "U13") (pin "1") (pinfunction "EN_1") (pintype "input"))
      (node (ref "U13") (pin "7") (pinfunction "VIN_7") (pintype "power_in"))
    )
    (net (code "12") (name "ADCS-3V3-") (class "Default")
      (node (ref "C34") (pin "1") (pinfunction "1_1") (pintype "passive"))
      (node (ref "R40") (pin "2") (pinfunction "2_2") (pintype "passive"))
      (node (ref "R41") (pin "1") (pinfunction "1_1") (pintype "passive"))
      (node (ref "U$12") (pin "4") (pinfunction "IN-_4") (pintype "bidirectional"))
      (node (ref "U5") (pin "2") (pinfunction "IN_2_2") (pintype "power_in"))
      (node (ref "U5") (pin "3") (pinfunction "IN_3") (pintype "power_in"))
    )
    (net (code "13") (name "ADCS-3V3-ADC") (class "Default")
      (node (ref "J5") (pin "4") (pinfunction "RTS_4") (pintype "bidirectional"))
      (node (ref "U$12") (pin "1") (pinfunction "OUT_1") (pintype "bidirectional"))
      (node (ref "U$21") (pin "8") (pinfunction "8_8") (pintype "bidirectional"))
      (node (ref "U15") (pin "4") (pinfunction "P6.7/CB7/A7_4") (pintype "bidirectional"))
    )
    (net (code "14") (name "ADCS-3V3-EN") (class "Default")
      (node (ref "U$21") (pin "7") (pinfunction "7_7") (pintype "bidirectional"))
      (node (ref "U15") (pin "31") (pinfunction "P2.2/TA2CLK/SMCLK_31") (pintype "bidirectional"))
      (node (ref "U5") (pin "4") (pinfunction "EN_4") (pintype "input"))
    )
    (net (code "15") (name "ADCS-5V-") (class "Default")
      (node (ref "C11") (pin "1") (pinfunction "1_1") (pintype "passive"))
      (node (ref "R37") (pin "2") (pinfunction "2_2") (pintype "passive"))
      (node (ref "R38") (pin "1") (pinfunction "1_1") (pintype "passive"))
      (node (ref "U$11") (pin "4") (pinfunction "IN-_4") (pintype "bidirectional"))
      (node (ref "U4") (pin "2") (pinfunction "IN_2_2") (pintype "power_in"))
      (node (ref "U4") (pin "3") (pinfunction "IN_3") (pintype "power_in"))
    )
    (net (code "16") (name "ADCS-5V-ADC") (class "Default")
      (node (ref "U$11") (pin "1") (pinfunction "OUT_1") (pintype "bidirectional"))
      (node (ref "U$21") (pin "17") (pinfunction "17_17") (pintype "bidirectional"))
      (node (ref "U15") (pin "3") (pinfunction "P6.6/CB6/A6_3") (pintype "bidirectional"))
    )
    (net (code "17") (name "ADCS-5V-EN") (class "Default")
      (node (ref "U$21") (pin "16") (pinfunction "16_16") (pintype "bidirectional"))
      (node (ref "U15") (pin "30") (pinfunction "P2.1/TA1.2_30") (pintype "bidirectional"))
      (node (ref "U4") (pin "4") (pinfunction "EN_4") (pintype "input"))
    )
    (net (code "18") (name "BAT-DIV-3") (class "Default")
      (node (ref "R17") (pin "1") (pinfunction "1_1") (pintype "passive"))
      (node (ref "R18") (pin "2") (pinfunction "2_2") (pintype "passive"))
      (node (ref "U$1") (pin "2") (pinfunction "IN1-_2") (pintype "passive"))
      (node (ref "U$1") (pin "5") (pinfunction "IN2+_5") (pintype "passive"))
      (node (ref "U$20") (pin "5") (pinfunction "5_5") (pintype "bidirectional"))
    )
    (net (code "19") (name "CHARGE-OK") (class "Default")
      (node (ref "R15") (pin "1") (pinfunction "1_1") (pintype "passive"))
      (node (ref "R24") (pin "1") (pinfunction "1_1") (pintype "passive"))
      (node (ref "U$1") (pin "1") (pinfunction "OUT1_1") (pintype "passive"))
      (node (ref "U$20") (pin "8") (pinfunction "8_8") (pintype "bidirectional"))
    )
    (net (code "20") (name "DISCHARGE-OK") (class "Default")
      (node (ref "R13") (pin "1") (pinfunction "1_1") (pintype "passive"))
      (node (ref "R25") (pin "1") (pinfunction "1_1") (pintype "passive"))
      (node (ref "U$1") (pin "7") (pinfunction "OUT2_7") (pintype "passive"))
      (node (ref "U$20") (pin "7") (pinfunction "7_7") (pintype "bidirectional"))
    )
    (net (code "21") (name "GND") (class "Default")
      (node (ref "C1") (pin "2") (pinfunction "2_2") (pintype "passive"))
      (node (ref "C10") (pin "2") (pinfunction "2_2") (pintype "passive"))
      (node (ref "C11") (pin "2") (pinfunction "2_2") (pintype "passive"))
      (node (ref "C12") (pin "2") (pinfunction "2_2") (pintype "passive"))
      (node (ref "C13") (pin "2") (pinfunction "2_2") (pintype "passive"))
      (node (ref "C14") (pin "2") (pinfunction "2_2") (pintype "passive"))
      (node (ref "C15") (pin "2") (pinfunction "2_2") (pintype "passive"))
      (node (ref "C16") (pin "2") (pinfunction "2_2") (pintype "passive"))
      (node (ref "C17") (pin "2") (pinfunction "2_2") (pintype "passive"))
      (node (ref "C18") (pin "2") (pinfunction "2_2") (pintype "passive"))
      (node (ref "C19") (pin "2") (pinfunction "2_2") (pintype "passive"))
      (node (ref "C2") (pin "2") (pinfunction "2_2") (pintype "passive"))
      (node (ref "C20") (pin "2") (pinfunction "2_2") (pintype "passive"))
      (node (ref "C21") (pin "2") (pinfunction "2_2") (pintype "passive"))
      (node (ref "C22") (pin "2") (pinfunction "2_2") (pintype "passive"))
      (node (ref "C23") (pin "2") (pinfunction "2_2") (pintype "passive"))
      (node (ref "C24") (pin "2") (pinfunction "2_2") (pintype "passive"))
      (node (ref "C25") (pin "2") (pinfunction "2_2") (pintype "passive"))
      (node (ref "C26") (pin "1") (pinfunction "1_1") (pintype "passive"))
      (node (ref "C27") (pin "1") (pinfunction "1_1") (pintype "passive"))
      (node (ref "C28") (pin "1") (pinfunction "1_1") (pintype "passive"))
      (node (ref "C29") (pin "1") (pinfunction "1_1") (pintype "passive"))
      (node (ref "C3") (pin "2") (pinfunction "2_2") (pintype "passive"))
      (node (ref "C30") (pin "2") (pinfunction "2_2") (pintype "passive"))
      (node (ref "C31") (pin "-") (pinfunction "-_-") (pintype "passive"))
      (node (ref "C32") (pin "2") (pinfunction "2_2") (pintype "passive"))
      (node (ref "C33") (pin "2") (pinfunction "2_2") (pintype "passive"))
      (node (ref "C34") (pin "2") (pinfunction "2_2") (pintype "passive"))
      (node (ref "C35") (pin "2") (pinfunction "2_2") (pintype "passive"))
      (node (ref "C38") (pin "2") (pinfunction "2_2") (pintype "passive"))
      (node (ref "C39") (pin "2") (pinfunction "2_2") (pintype "passive"))
      (node (ref "C4") (pin "1") (pinfunction "1_1") (pintype "passive"))
      (node (ref "C40") (pin "2") (pinfunction "2_2") (pintype "passive"))
      (node (ref "C41") (pin "2") (pinfunction "2_2") (pintype "passive"))
      (node (ref "C42") (pin "2") (pinfunction "2_2") (pintype "passive"))
      (node (ref "C43") (pin "2") (pinfunction "2_2") (pintype "passive"))
      (node (ref "C44") (pin "2") (pinfunction "2_2") (pintype "passive"))
      (node (ref "C45") (pin "2") (pinfunction "2_2") (pintype "passive"))
      (node (ref "C5") (pin "2") (pinfunction "2_2") (pintype "passive"))
      (node (ref "C6") (pin "2") (pinfunction "2_2") (pintype "passive"))
      (node (ref "C7") (pin "2") (pinfunction "2_2") (pintype "passive"))
      (node (ref "C8") (pin "2") (pinfunction "2_2") (pintype "passive"))
      (node (ref "C9") (pin "2") (pinfunction "2_2") (pintype "passive"))
      (node (ref "J5") (pin "1") (pinfunction "GND_1") (pintype "bidirectional"))
      (node (ref "Q1") (pin "2") (pinfunction "S_2") (pintype "passive"))
      (node (ref "R10") (pin "1") (pinfunction "1_1") (pintype "passive"))
      (node (ref "R14") (pin "1") (pinfunction "1_1") (pintype "passive"))
      (node (ref "R16") (pin "1") (pinfunction "1_1") (pintype "passive"))
      (node (ref "R18") (pin "1") (pinfunction "1_1") (pintype "passive"))
      (node (ref "R20") (pin "1") (pinfunction "1_1") (pintype "passive"))
      (node (ref "R22") (pin "1") (pinfunction "1_1") (pintype "passive"))
      (node (ref "R26") (pin "1") (pinfunction "1_1") (pintype "passive"))
      (node (ref "R29") (pin "1") (pinfunction "1_1") (pintype "passive"))
      (node (ref "R3") (pin "1") (pinfunction "1_1") (pintype "passive"))
      (node (ref "R32") (pin "1") (pinfunction "1_1") (pintype "passive"))
      (node (ref "R34") (pin "1") (pinfunction "1_1") (pintype "passive"))
      (node (ref "R36") (pin "1") (pinfunction "1_1") (pintype "passive"))
      (node (ref "R39") (pin "1") (pinfunction "1_1") (pintype "passive"))
      (node (ref "R44") (pin "1") (pinfunction "1_1") (pintype "passive"))
      (node (ref "R45") (pin "1") (pinfunction "1_1") (pintype "passive"))
      (node (ref "R5") (pin "1") (pinfunction "1_1") (pintype "passive"))
      (node (ref "R6") (pin "1") (pinfunction "1_1") (pintype "passive"))
      (node (ref "S1") (pin "3") (pinfunction "P_3") (pintype "passive"))
      (node (ref "S1") (pin "4") (pinfunction "P1_4") (pintype "passive"))
      (node (ref "U$1") (pin "4") (pinfunction "VCC-_4") (pintype "passive"))
      (node (ref "U$10") (pin "2") (pinfunction "GND_2") (pintype "bidirectional"))
      (node (ref "U$10") (pin "5") (pinfunction "REF_5") (pintype "bidirectional"))
      (node (ref "U$11") (pin "2") (pinfunction "GND_2") (pintype "bidirectional"))
      (node (ref "U$11") (pin "5") (pinfunction "REF_5") (pintype "bidirectional"))
      (node (ref "U$12") (pin "2") (pinfunction "GND_2") (pintype "bidirectional"))
      (node (ref "U$12") (pin "5") (pinfunction "REF_5") (pintype "bidirectional"))
      (node (ref "U$13") (pin "2") (pinfunction "GND_2") (pintype "bidirectional"))
      (node (ref "U$13") (pin "5") (pinfunction "REF_5") (pintype "bidirectional"))
      (node (ref "U$14") (pin "2") (pinfunction "GND_2") (pintype "bidirectional"))
      (node (ref "U$14") (pin "5") (pinfunction "REF_5") (pintype "bidirectional"))
      (node (ref "U$15") (pin "1") (pinfunction "A1_1") (pintype "bidirectional"))
      (node (ref "U$16") (pin "1") (pinfunction "A1_1") (pintype "bidirectional"))
      (node (ref "U$17") (pin "1") (pinfunction "A1_1") (pintype "bidirectional"))
      (node (ref "U$18") (pin "1") (pinfunction "A1_1") (pintype "bidirectional"))
      (node (ref "U$19") (pin "1") (pinfunction "A1_1") (pintype "bidirectional"))
      (node (ref "U$20") (pin "10") (pinfunction "10_10") (pintype "bidirectional"))
      (node (ref "U$24") (pin "2") (pinfunction "A2_2") (pintype "bidirectional"))
      (node (ref "U$25") (pin "2") (pinfunction "A2_2") (pintype "bidirectional"))
      (node (ref "U$7") (pin "2") (pinfunction "A2_2") (pintype "bidirectional"))
      (node (ref "U$8") (pin "2") (pinfunction "GND_2") (pintype "bidirectional"))
      (node (ref "U$8") (pin "5") (pinfunction "REF_5") (pintype "bidirectional"))
      (node (ref "U$9") (pin "1") (pinfunction "A1_1") (pintype "bidirectional"))
      (node (ref "U1") (pin "2") (pinfunction "GND_2") (pintype "passive"))
      (node (ref "U11") (pin "11") (pinfunction "GND_11") (pintype "power_in"))
      (node (ref "U12") (pin "1") (pinfunction "RST/~{RST}_1") (pintype "bidirectional"))
      (node (ref "U12") (pin "2") (pinfunction "GND_2") (pintype "power_in"))
      (node (ref "U13") (pin "5") (pinfunction "GND_5") (pintype "power_in"))
      (node (ref "U14") (pin "1") (pinfunction "GND_1") (pintype "power_in"))
      (node (ref "U14") (pin "9") (pinfunction "PAD_9") (pintype "power_in"))
      (node (ref "U15") (pin "14") (pinfunction "AVSS1_14") (pintype "bidirectional"))
      (node (ref "U15") (pin "19") (pinfunction "DVSS1_19") (pintype "bidirectional"))
      (node (ref "U15") (pin "49") (pinfunction "DVSS2_49") (pintype "bidirectional"))
      (node (ref "U15") (pin "61") (pinfunction "VSSU_61") (pintype "bidirectional"))
      (node (ref "U15") (pin "65") (pinfunction "VBUS_65") (pintype "bidirectional"))
      (node (ref "U15") (pin "68") (pinfunction "AVSS2_68") (pintype "bidirectional"))
      (node (ref "U16") (pin "2") (pinfunction "S_2") (pintype "passive"))
      (node (ref "U17") (pin "1") (pinfunction "GND_1") (pintype "power_in"))
      (node (ref "U17") (pin "9") (pinfunction "PAD_9") (pintype "power_in"))
      (node (ref "U2") (pin "1") (pinfunction "GND_1") (pintype "power_in"))
      (node (ref "U2") (pin "9") (pinfunction "PAD_9") (pintype "power_in"))
      (node (ref "U3") (pin "1") (pinfunction "GND_1") (pintype "power_in"))
      (node (ref "U3") (pin "9") (pinfunction "PAD_9") (pintype "power_in"))
      (node (ref "U4") (pin "1") (pinfunction "GND_1") (pintype "power_in"))
      (node (ref "U4") (pin "9") (pinfunction "PAD_9") (pintype "power_in"))
      (node (ref "U5") (pin "1") (pinfunction "GND_1") (pintype "power_in"))
      (node (ref "U5") (pin "9") (pinfunction "PAD_9") (pintype "power_in"))
      (node (ref "U7") (pin "1") (pinfunction "GND_1") (pintype "power_in"))
      (node (ref "U7") (pin "9") (pinfunction "PAD_9") (pintype "power_in"))
      (node (ref "U9") (pin "1") (pinfunction "GND_1") (pintype "power_in"))
      (node (ref "U9") (pin "9") (pinfunction "PAD_9") (pintype "power_in"))
      (node (ref "Y1") (pin "P3") (pinfunction "GND_P3") (pintype "power_in"))
      (node (ref "Y2") (pin "2") (pinfunction "2_2") (pintype "passive"))
    )
    (net (code "22") (name "GPS-3V3-") (class "Default")
      (node (ref "C45") (pin "1") (pinfunction "1_1") (pintype "passive"))
      (node (ref "R48") (pin "2") (pinfunction "2_2") (pintype "passive"))
      (node (ref "R49") (pin "1") (pinfunction "1_1") (pintype "passive"))
      (node (ref "U$13") (pin "4") (pinfunction "IN-_4") (pintype "bidirectional"))
      (node (ref "U14") (pin "2") (pinfunction "IN_2_2") (pintype "power_in"))
      (node (ref "U14") (pin "3") (pinfunction "IN_3") (pintype "power_in"))
    )
    (net (code "23") (name "GPS-3V3-ADC") (class "Default")
      (node (ref "U$13") (pin "1") (pinfunction "OUT_1") (pintype "bidirectional"))
      (node (ref "U$21") (pin "20") (pinfunction "20_20") (pintype "bidirectional"))
      (node (ref "U15") (pin "5") (pinfunction "P7.0/CB8/A12_5") (pintype "bidirectional"))
    )
    (net (code "24") (name "GPS-3V3-EN") (class "Default")
      (node (ref "U$21") (pin "19") (pinfunction "19_19") (pintype "bidirectional"))
      (node (ref "U14") (pin "4") (pinfunction "EN_4") (pintype "input"))
      (node (ref "U15") (pin "32") (pinfunction "P2.3/TA2.0_32") (pintype "bidirectional"))
    )
    (net (code "25") (name "MAIN-POWER-BUS") (class "Default")
      (node (ref "C17") (pin "1") (pinfunction "1_1") (pintype "passive"))
      (node (ref "R23") (pin "2") (pinfunction "2_2") (pintype "passive"))
      (node (ref "U$2") (pin "1") (pinfunction "S_1") (pintype "bidirectional"))
      (node (ref "U$2") (pin "2") (pinfunction "S_2") (pintype "bidirectional"))
      (node (ref "U$2") (pin "3") (pinfunction "S_3") (pintype "bidirectional"))
      (node (ref "U$20") (pin "9") (pinfunction "9_9") (pintype "bidirectional"))
      (node (ref "U$24") (pin "1") (pinfunction "A1_1") (pintype "bidirectional"))
      (node (ref "U10") (pin "2") (pinfunction "K_2") (pintype "passive"))
      (node (ref "U9") (pin "2") (pinfunction "IN_2_2") (pintype "power_in"))
      (node (ref "U9") (pin "3") (pinfunction "IN_3") (pintype "power_in"))
    )
    (net (code "26") (name "MSP_OBC_RESET") (class "Default")
      (node (ref "Q1") (pin "1") (pinfunction "G_1") (pintype "passive"))
      (node (ref "R36") (pin "2") (pinfunction "2_2") (pintype "passive"))
      (node (ref "U$22") (pin "2") (pinfunction "2_2") (pintype "bidirectional"))
    )
    (net (code "27") (name "Net-(R27-Pad2)") (class "Default")
      (node (ref "R27") (pin "2") (pinfunction "2_2") (pintype "passive"))
      (node (ref "U$2") (pin "5") (pinfunction "D_5") (pintype "bidirectional"))
      (node (ref "U$2") (pin "6") (pinfunction "D_6") (pintype "bidirectional"))
      (node (ref "U$2") (pin "7") (pinfunction "D_7") (pintype "bidirectional"))
      (node (ref "U$2") (pin "8") (pinfunction "D_8") (pintype "bidirectional"))
      (node (ref "U$3") (pin "1") (pinfunction "S_1") (pintype "bidirectional"))
      (node (ref "U$3") (pin "2") (pinfunction "S_2") (pintype "bidirectional"))
      (node (ref "U$3") (pin "3") (pinfunction "S_3") (pintype "bidirectional"))
    )
    (net (code "28") (name "Net-(U$2-G)") (class "Default")
      (node (ref "R23") (pin "1") (pinfunction "1_1") (pintype "passive"))
      (node (ref "R27") (pin "1") (pinfunction "1_1") (pintype "passive"))
      (node (ref "U$2") (pin "4") (pinfunction "G_4") (pintype "bidirectional"))
      (node (ref "U$3") (pin "4") (pinfunction "G_4") (pintype "bidirectional"))
      (node (ref "U$7") (pin "1") (pinfunction "A1_1") (pintype "bidirectional"))
    )
    (net (code "29") (name "Net-(U$4-G)") (class "Default")
      (node (ref "R31") (pin "1") (pinfunction "1_1") (pintype "passive"))
      (node (ref "U$4") (pin "4") (pinfunction "G_4") (pintype "bidirectional"))
      (node (ref "U16") (pin "3") (pinfunction "D_3") (pintype "passive"))
    )
    (net (code "30") (name "Net-(U2-ILIM)") (class "Default")
      (node (ref "R5") (pin "2") (pinfunction "2_2") (pintype "passive"))
      (node (ref "U2") (pin "5") (pinfunction "ILIM_5") (pintype "input"))
    )
    (net (code "31") (name "Net-(U2-~{FAULT})") (class "Default")
      (node (ref "R2") (pin "2") (pinfunction "2_2") (pintype "passive"))
      (node (ref "R7") (pin "1") (pinfunction "1_1") (pintype "passive"))
      (node (ref "U2") (pin "8") (pinfunction "~{FAULT}_8") (pintype "open_collector"))
    )
    (net (code "32") (name "Net-(U3-ILIM)") (class "Default")
      (node (ref "R10") (pin "2") (pinfunction "2_2") (pintype "passive"))
      (node (ref "U3") (pin "5") (pinfunction "ILIM_5") (pintype "input"))
    )
    (net (code "33") (name "Net-(U4-ILIM)") (class "Default")
      (node (ref "R26") (pin "2") (pinfunction "2_2") (pintype "passive"))
      (node (ref "U4") (pin "5") (pinfunction "ILIM_5") (pintype "input"))
    )
    (net (code "34") (name "Net-(U4-~{FAULT})") (class "Default")
      (node (ref "R37") (pin "1") (pinfunction "1_1") (pintype "passive"))
      (node (ref "R8") (pin "2") (pinfunction "2_2") (pintype "passive"))
      (node (ref "U4") (pin "8") (pinfunction "~{FAULT}_8") (pintype "open_collector"))
    )
    (net (code "35") (name "Net-(U5-ILIM)") (class "Default")
      (node (ref "R39") (pin "2") (pinfunction "2_2") (pintype "passive"))
      (node (ref "U5") (pin "5") (pinfunction "ILIM_5") (pintype "input"))
    )
    (net (code "36") (name "Net-(U7-EN)") (class "Default")
      (node (ref "C13") (pin "1") (pinfunction "1_1") (pintype "passive"))
      (node (ref "R13") (pin "2") (pinfunction "2_2") (pintype "passive"))
      (node (ref "U7") (pin "4") (pinfunction "EN_4") (pintype "input"))
      (node (ref "U7") (pin "8") (pinfunction "~{FAULT}_8") (pintype "open_collector"))
    )
    (net (code "37") (name "Net-(U7-ILIM)") (class "Default")
      (node (ref "R14") (pin "2") (pinfunction "2_2") (pintype "passive"))
      (node (ref "U7") (pin "5") (pinfunction "ILIM_5") (pintype "input"))
    )
    (net (code "38") (name "Net-(U9-EN)") (class "Default")
      (node (ref "C14") (pin "1") (pinfunction "1_1") (pintype "passive"))
      (node (ref "R15") (pin "2") (pinfunction "2_2") (pintype "passive"))
      (node (ref "U9") (pin "4") (pinfunction "EN_4") (pintype "input"))
      (node (ref "U9") (pin "8") (pinfunction "~{FAULT}_8") (pintype "open_collector"))
    )
    (net (code "39") (name "Net-(U9-ILIM)") (class "Default")
      (node (ref "R16") (pin "2") (pinfunction "2_2") (pintype "passive"))
      (node (ref "U9") (pin "5") (pinfunction "ILIM_5") (pintype "input"))
    )
    (net (code "40") (name "Net-(U10-A)") (class "Default")
      (node (ref "C15") (pin "1") (pinfunction "1_1") (pintype "passive"))
      (node (ref "U10") (pin "3") (pinfunction "A_3") (pintype "passive"))
      (node (ref "U7") (pin "6") (pinfunction "OUT_2_6") (pintype "power_in"))
      (node (ref "U7") (pin "7") (pinfunction "OUT_7") (pintype "power_in"))
      (node (ref "U8") (pin "3") (pinfunction "A_3") (pintype "passive"))
      (node (ref "U9") (pin "6") (pinfunction "OUT_2_6") (pintype "power_in"))
      (node (ref "U9") (pin "7") (pinfunction "OUT_7") (pintype "power_in"))
    )
    (net (code "41") (name "Net-(U11-SS)") (class "Default")
      (node (ref "C5") (pin "1") (pinfunction "1_1") (pintype "passive"))
      (node (ref "U11") (pin "6") (pinfunction "SS_6") (pintype "input"))
    )
    (net (code "42") (name "Net-(U11-SW)") (class "Default")
      (node (ref "L1") (pin "1") (pinfunction "1_1") (pintype "passive"))
      (node (ref "U11") (pin "1") (pinfunction "SW_2_1") (pintype "power_in"))
      (node (ref "U11") (pin "2") (pinfunction "SW_2") (pintype "power_in"))
    )
    (net (code "43") (name "Net-(U12-DIV)") (class "Default")
      (node (ref "R28") (pin "1") (pinfunction "1_1") (pintype "passive"))
      (node (ref "R29") (pin "2") (pinfunction "2_2") (pintype "passive"))
      (node (ref "U12") (pin "4") (pinfunction "DIV_4") (pintype "input"))
    )
    (net (code "44") (name "Net-(U12-OUT)") (class "Default")
      (node (ref "R30") (pin "2") (pinfunction "2_2") (pintype "passive"))
      (node (ref "R32") (pin "2") (pinfunction "2_2") (pintype "passive"))
      (node (ref "U12") (pin "6") (pinfunction "OUT_6") (pintype "output"))
      (node (ref "U16") (pin "1") (pinfunction "G_1") (pintype "passive"))
    )
    (net (code "45") (name "Net-(U12-SET)") (class "Default")
      (node (ref "R30") (pin "1") (pinfunction "1_1") (pintype "passive"))
      (node (ref "U12") (pin "3") (pinfunction "SET_3") (pintype "input"))
    )
    (net (code "46") (name "Net-(U12-V+)") (class "Default")
      (node (ref "C1") (pin "1") (pinfunction "1_1") (pintype "passive"))
      (node (ref "R28") (pin "2") (pinfunction "2_2") (pintype "passive"))
      (node (ref "R31") (pin "2") (pinfunction "2_2") (pintype "passive"))
      (node (ref "U$3") (pin "5") (pinfunction "D_5") (pintype "bidirectional"))
      (node (ref "U$3") (pin "6") (pinfunction "D_6") (pintype "bidirectional"))
      (node (ref "U$3") (pin "7") (pinfunction "D_7") (pintype "bidirectional"))
      (node (ref "U$3") (pin "8") (pinfunction "D_8") (pintype "bidirectional"))
      (node (ref "U$4") (pin "1") (pinfunction "S_1") (pintype "bidirectional"))
      (node (ref "U$4") (pin "2") (pinfunction "S_2") (pintype "bidirectional"))
      (node (ref "U$4") (pin "3") (pinfunction "S_3") (pintype "bidirectional"))
      (node (ref "U12") (pin "5") (pinfunction "V+_5") (pintype "power_in"))
    )
    (net (code "47") (name "Net-(U13-PG)") (class "Default")
      (node (ref "R33") (pin "2") (pinfunction "2_2") (pintype "passive"))
      (node (ref "U13") (pin "2") (pinfunction "PG_2") (pintype "output"))
    )
    (net (code "48") (name "Net-(U13-SW)") (class "Default")
      (node (ref "U$5") (pin "2") (pinfunction "2_2") (pintype "passive"))
      (node (ref "U13") (pin "6") (pinfunction "SW_6") (pintype "power_in"))
    )
    (net (code "49") (name "Net-(U14-ILIM)") (class "Default")
      (node (ref "R44") (pin "2") (pinfunction "2_2") (pintype "passive"))
      (node (ref "U14") (pin "5") (pinfunction "ILIM_5") (pintype "input"))
    )
    (net (code "50") (name "Net-(U15-AVCC1)") (class "Default")
      (node (ref "C30") (pin "1") (pinfunction "1_1") (pintype "passive"))
      (node (ref "R4") (pin "1") (pinfunction "1_1") (pintype "passive"))
      (node (ref "U15") (pin "11") (pinfunction "AVCC1_11") (pintype "bidirectional"))
    )
    (net (code "51") (name "Net-(U15-P3.0{slash}UCB0SIMO{slash}UCB0SDA)") (class "Default")
      (node (ref "U$23") (pin "3") (pinfunction "3_3") (pintype "bidirectional"))
      (node (ref "U15") (pin "37") (pinfunction "P3.0/UCB0SIMO/UCB0SDA_37") (pintype "bidirectional"))
    )
    (net (code "52") (name "Net-(U15-P3.1{slash}UCB0SOMI{slash}UCB0SCL)") (class "Default")
      (node (ref "U$23") (pin "2") (pinfunction "2_2") (pintype "bidirectional"))
      (node (ref "U15") (pin "38") (pinfunction "P3.1/UCB0SOMI/UCB0SCL_38") (pintype "bidirectional"))
    )
    (net (code "53") (name "Net-(U15-P3.2{slash}UCB0CLK{slash}UCA0STE)") (class "Default")
      (node (ref "U$23") (pin "1") (pinfunction "1_1") (pintype "bidirectional"))
      (node (ref "U15") (pin "39") (pinfunction "P3.2/UCB0CLK/UCA0STE_39") (pintype "bidirectional"))
    )
    (net (code "54") (name "Net-(U15-P5.2{slash}XT2IN)") (class "Default")
      (node (ref "U15") (pin "69") (pinfunction "P5.2/XT2IN_69") (pintype "bidirectional"))
      (node (ref "Y2") (pin "3") (pinfunction "3_3") (pintype "passive"))
    )
    (net (code "55") (name "Net-(U15-P5.3{slash}XT2OUT)") (class "Default")
      (node (ref "U15") (pin "70") (pinfunction "P5.3/XT2OUT_70") (pintype "bidirectional"))
      (node (ref "Y2") (pin "1") (pinfunction "1_1") (pintype "passive"))
    )
    (net (code "56") (name "Net-(U15-P5.4{slash}XIN)") (class "Default")
      (node (ref "C29") (pin "2") (pinfunction "2_2") (pintype "passive"))
      (node (ref "U15") (pin "12") (pinfunction "P5.4/XIN_12") (pintype "bidirectional"))
      (node (ref "Y1") (pin "P2") (pinfunction "2_P2") (pintype "bidirectional"))
    )
    (net (code "57") (name "Net-(U15-P5.5{slash}XOUT)") (class "Default")
      (node (ref "C28") (pin "2") (pinfunction "2_2") (pintype "passive"))
      (node (ref "U15") (pin "13") (pinfunction "P5.5/XOUT_13") (pintype "bidirectional"))
      (node (ref "Y1") (pin "P1") (pinfunction "1_P1") (pintype "bidirectional"))
    )
    (net (code "58") (name "Net-(U15-PUR)") (class "Default")
      (node (ref "R6") (pin "2") (pinfunction "2_2") (pintype "passive"))
      (node (ref "U15") (pin "63") (pinfunction "PUR_63") (pintype "bidirectional"))
    )
    (net (code "59") (name "Net-(U15-VCORE)") (class "Default")
      (node (ref "C26") (pin "2") (pinfunction "2_2") (pintype "passive"))
      (node (ref "U15") (pin "20") (pinfunction "VCORE_20") (pintype "bidirectional"))
    )
    (net (code "60") (name "Net-(U17-ILIM)") (class "Default")
      (node (ref "R45") (pin "2") (pinfunction "2_2") (pintype "passive"))
      (node (ref "U17") (pin "5") (pinfunction "ILIM_5") (pintype "input"))
    )
    (net (code "61") (name "OBC-3V3-") (class "Default")
      (node (ref "C8") (pin "1") (pinfunction "1_1") (pintype "passive"))
      (node (ref "R11") (pin "2") (pinfunction "2_2") (pintype "passive"))
      (node (ref "R12") (pin "1") (pinfunction "1_1") (pintype "passive"))
      (node (ref "U$10") (pin "4") (pinfunction "IN-_4") (pintype "bidirectional"))
      (node (ref "U3") (pin "2") (pinfunction "IN_2_2") (pintype "power_in"))
      (node (ref "U3") (pin "3") (pinfunction "IN_3") (pintype "power_in"))
    )
    (net (code "62") (name "OBC-3V3-ADC") (class "Default")
      (node (ref "U$10") (pin "1") (pinfunction "OUT_1") (pintype "bidirectional"))
      (node (ref "U$21") (pin "5") (pinfunction "5_5") (pintype "bidirectional"))
      (node (ref "U15") (pin "2") (pinfunction "P6.5/CB5/A5_2") (pintype "bidirectional"))
    )
    (net (code "63") (name "OBC-3V3-EN") (class "Default")
      (node (ref "U$21") (pin "4") (pinfunction "4_4") (pintype "bidirectional"))
      (node (ref "U15") (pin "29") (pinfunction "P2.0/TA1.1_29") (pintype "bidirectional"))
      (node (ref "U3") (pin "4") (pinfunction "EN_4") (pintype "input"))
    )
    (net (code "64") (name "OBC-5V-") (class "Default")
      (node (ref "C3") (pin "1") (pinfunction "1_1") (pintype "passive"))
      (node (ref "R7") (pin "2") (pinfunction "2_2") (pintype "passive"))
      (node (ref "R9") (pin "1") (pinfunction "1_1") (pintype "passive"))
      (node (ref "U$8") (pin "4") (pinfunction "IN-_4") (pintype "bidirectional"))
      (node (ref "U2") (pin "2") (pinfunction "IN_2_2") (pintype "power_in"))
      (node (ref "U2") (pin "3") (pinfunction "IN_3") (pintype "power_in"))
    )
    (net (code "65") (name "OBC-5V-ADC") (class "Default")
      (node (ref "U$21") (pin "14") (pinfunction "14_14") (pintype "bidirectional"))
      (node (ref "U$8") (pin "1") (pinfunction "OUT_1") (pintype "bidirectional"))
      (node (ref "U15") (pin "1") (pinfunction "P6.4/CB4/A4_1") (pintype "bidirectional"))
    )
    (net (code "66") (name "OBC-5V-EN") (class "Default")
      (node (ref "J5") (pin "5") (pinfunction "CTS_5") (pintype "bidirectional"))
      (node (ref "U$21") (pin "13") (pinfunction "13_13") (pintype "bidirectional"))
      (node (ref "U15") (pin "28") (pinfunction "P1.7/TA1.0_28") (pintype "bidirectional"))
      (node (ref "U2") (pin "4") (pinfunction "EN_4") (pintype "input"))
    )
    (net (code "67") (name "P4.4{slash}UCA1TXD") (class "Default")
      (node (ref "J5") (pin "7") (pinfunction "TXD_7") (pintype "bidirectional"))
      (node (ref "U15") (pin "51") (pinfunction "P4.4/PM_UCA1TXD/PM_UCA1SIMO_51") (pintype "bidirectional"))
    )
    (net (code "68") (name "P4.5{slash}UCA1RXD") (class "Default")
      (node (ref "J5") (pin "6") (pinfunction "RXD_6") (pintype "bidirectional"))
      (node (ref "U15") (pin "52") (pinfunction "P4.5/PM_UCA1RXD/PM_UCA1SOMI_52") (pintype "bidirectional"))
    )
    (net (code "69") (name "PACK-IN") (class "Default")
      (node (ref "C16") (pin "1") (pinfunction "1_1") (pintype "passive"))
      (node (ref "C18") (pin "1") (pinfunction "1_1") (pintype "passive"))
      (node (ref "R17") (pin "2") (pinfunction "2_2") (pintype "passive"))
      (node (ref "U$1") (pin "8") (pinfunction "VCC+_8") (pintype "passive"))
      (node (ref "U$20") (pin "1") (pinfunction "1_1") (pintype "bidirectional"))
      (node (ref "U$25") (pin "1") (pinfunction "A1_1") (pintype "bidirectional"))
      (node (ref "U1") (pin "3") (pinfunction "EN_3") (pintype "passive"))
      (node (ref "U1") (pin "4") (pinfunction "VIN_4") (pintype "input"))
      (node (ref "U7") (pin "2") (pinfunction "IN_2_2") (pintype "power_in"))
      (node (ref "U7") (pin "3") (pinfunction "IN_3") (pintype "power_in"))
      (node (ref "U8") (pin "2") (pinfunction "K_2") (pintype "passive"))
    )
    (net (code "70") (name "RESERVED1") (class "Default")
      (node (ref "U$22") (pin "4") (pinfunction "4_4") (pintype "bidirectional"))
      (node (ref "U15") (pin "53") (pinfunction "P4.6/PM_NONE_53") (pintype "bidirectional"))
    )
    (net (code "71") (name "RESERVED2") (class "Default")
      (node (ref "U$22") (pin "5") (pinfunction "5_5") (pintype "bidirectional"))
      (node (ref "U15") (pin "54") (pinfunction "P4.7/PM_NONE_54") (pintype "bidirectional"))
    )
    (net (code "72") (name "RESERVED3") (class "Default")
      (node (ref "U$22") (pin "6") (pinfunction "6_6") (pintype "bidirectional"))
      (node (ref "U15") (pin "55") (pinfunction "P5.6/TB0.0_55") (pintype "bidirectional"))
    )
    (net (code "73") (name "RESERVED4") (class "Default")
      (node (ref "U$22") (pin "7") (pinfunction "7\\_7") (pintype "bidirectional"))
      (node (ref "U15") (pin "56") (pinfunction "P5.7/TB0.1_56") (pintype "bidirectional"))
    )
    (net (code "74") (name "RESERVED5") (class "Default")
      (node (ref "U$22") (pin "8") (pinfunction "8_8") (pintype "bidirectional"))
      (node (ref "U15") (pin "57") (pinfunction "P7.4/TB0.2_57") (pintype "bidirectional"))
    )
    (net (code "75") (name "RESERVED6") (class "Default")
      (node (ref "U$22") (pin "9") (pinfunction "9_9") (pintype "bidirectional"))
      (node (ref "U15") (pin "58") (pinfunction "P7.5/TB0.3_58") (pintype "bidirectional"))
    )
    (net (code "76") (name "RESERVED7") (class "Default")
      (node (ref "U$22") (pin "10") (pinfunction "10_10") (pintype "bidirectional"))
      (node (ref "U15") (pin "59") (pinfunction "P7.6/TB0.4_59") (pintype "bidirectional"))
    )
    (net (code "77") (name "RF-3V3-") (class "Default")
      (node (ref "C40") (pin "1") (pinfunction "1_1") (pintype "passive"))
      (node (ref "R46") (pin "2") (pinfunction "2_2") (pintype "passive"))
      (node (ref "R47") (pin "1") (pinfunction "1_1") (pintype "passive"))
      (node (ref "U$14") (pin "4") (pinfunction "IN-_4") (pintype "bidirectional"))
      (node (ref "U17") (pin "2") (pinfunction "IN_2_2") (pintype "power_in"))
      (node (ref "U17") (pin "3") (pinfunction "IN_3") (pintype "power_in"))
    )
    (net (code "78") (name "RF-3V3-ADC") (class "Default")
      (node (ref "U$14") (pin "1") (pinfunction "OUT_1") (pintype "bidirectional"))
      (node (ref "U$21") (pin "11") (pinfunction "11_11") (pintype "bidirectional"))
      (node (ref "U15") (pin "6") (pinfunction "P7.1/CB9/A13_6") (pintype "bidirectional"))
    )
    (net (code "79") (name "RF-3V3-EN") (class "Default")
      (node (ref "U$21") (pin "10") (pinfunction "10_10") (pintype "bidirectional"))
      (node (ref "U15") (pin "33") (pinfunction "P2.4/TA2.1_33") (pintype "bidirectional"))
      (node (ref "U17") (pin "4") (pinfunction "EN_4") (pintype "input"))
    )
    (net (code "80") (name "RST{slash}SBWTDIO") (class "Default")
      (node (ref "C25") (pin "1") (pinfunction "1_1") (pintype "passive"))
      (node (ref "J5") (pin "8") (pinfunction "SBWTDIO_8") (pintype "bidirectional"))
      (node (ref "Q1") (pin "3") (pinfunction "D_3") (pintype "passive"))
      (node (ref "R1") (pin "1") (pinfunction "1_1") (pintype "passive"))
      (node (ref "S1") (pin "1") (pinfunction "S_1") (pintype "passive"))
      (node (ref "S1") (pin "2") (pinfunction "S1_2") (pintype "passive"))
      (node (ref "U15") (pin "76") (pinfunction "RST/NMI/SBWTDIO_76") (pintype "bidirectional"))
    )
    (net (code "81") (name "TEST{slash}SBWTCK") (class "Default")
      (node (ref "J5") (pin "9") (pinfunction "SBWTCK_9") (pintype "bidirectional"))
      (node (ref "U15") (pin "71") (pinfunction "TEST/SBWTCK_71") (pintype "bidirectional"))
    )
    (net (code "82") (name "UCA0RXD") (class "Default")
      (node (ref "U$22") (pin "3") (pinfunction "3_3") (pintype "bidirectional"))
      (node (ref "U15") (pin "41") (pinfunction "P3.4/UCA0RXD/UCA0SOMI_41") (pintype "bidirectional"))
    )
    (net (code "83") (name "UCA0TXD") (class "Default")
      (node (ref "U$22") (pin "1") (pinfunction "1_1") (pintype "bidirectional"))
      (node (ref "U15") (pin "40") (pinfunction "P3.3/UCA0TXD/UCA0SIMO_40") (pintype "bidirectional"))
    )
    (net (code "84") (name "VOLTAGE-REGULATOR-INPUT") (class "Default")
      (node (ref "C21") (pin "1") (pinfunction "1_1") (pintype "passive"))
      (node (ref "C22") (pin "1") (pinfunction "1_1") (pintype "passive"))
      (node (ref "C23") (pin "1") (pinfunction "1_1") (pintype "passive"))
      (node (ref "L1") (pin "2") (pinfunction "2_2") (pintype "passive"))
      (node (ref "U$4") (pin "5") (pinfunction "D_5") (pintype "bidirectional"))
      (node (ref "U$4") (pin "6") (pinfunction "D_6") (pintype "bidirectional"))
      (node (ref "U$4") (pin "7") (pinfunction "D_7") (pintype "bidirectional"))
      (node (ref "U$4") (pin "8") (pinfunction "D_8") (pintype "bidirectional"))
      (node (ref "U11") (pin "10") (pinfunction "VIN_10") (pintype "power_in"))
      (node (ref "U11") (pin "9") (pinfunction "EN_9") (pintype "input"))
    )
    (net (code "85") (name "unconnected-(J5-5V-Pad2)") (class "Default")
      (node (ref "J5") (pin "2") (pinfunction "5V_2") (pintype "bidirectional"))
    )
    (net (code "86") (name "unconnected-(J5-NC-Pad10)") (class "Default")
      (node (ref "J5") (pin "10") (pinfunction "NC_10") (pintype "bidirectional"))
    )
    (net (code "87") (name "unconnected-(MH1-MOUNT-Pad1)") (class "Default")
      (node (ref "MH1") (pin "1") (pinfunction "MOUNT_1") (pintype "no_connect"))
    )
    (net (code "88") (name "unconnected-(MH2-MOUNT-Pad1)") (class "Default")
      (node (ref "MH2") (pin "1") (pinfunction "MOUNT_1") (pintype "no_connect"))
    )
    (net (code "89") (name "unconnected-(MH3-MOUNT-Pad1)") (class "Default")
      (node (ref "MH3") (pin "1") (pinfunction "MOUNT_1") (pintype "no_connect"))
    )
    (net (code "90") (name "unconnected-(MH4-MOUNT-Pad1)") (class "Default")
      (node (ref "MH4") (pin "1") (pinfunction "MOUNT_1") (pintype "no_connect"))
    )
    (net (code "91") (name "unconnected-(U$20-Pad6)") (class "Default")
      (node (ref "U$20") (pin "6") (pinfunction "6_6") (pintype "bidirectional"))
    )
    (net (code "92") (name "unconnected-(U1-REF-Pad1)") (class "Default")
      (node (ref "U1") (pin "1") (pinfunction "REF_1") (pintype "passive"))
    )
    (net (code "93") (name "unconnected-(U8-NC-Pad1)") (class "Default")
      (node (ref "U8") (pin "1") (pinfunction "NC_1") (pintype "no_connect"))
    )
    (net (code "94") (name "unconnected-(U10-NC-Pad1)") (class "Default")
      (node (ref "U10") (pin "1") (pinfunction "NC_1") (pintype "no_connect"))
    )
    (net (code "95") (name "unconnected-(U11-HYS-Pad8)") (class "Default")
      (node (ref "U11") (pin "8") (pinfunction "HYS_8") (pintype "output"))
    )
    (net (code "96") (name "unconnected-(U11-PG-Pad5)") (class "Default")
      (node (ref "U11") (pin "5") (pinfunction "PG_5") (pintype "output"))
    )
    (net (code "97") (name "unconnected-(U15-P1.6{slash}TA1CLK{slash}CBOUT-Pad27)") (class "Default")
      (node (ref "U15") (pin "27") (pinfunction "P1.6/TA1CLK/CBOUT_27") (pintype "bidirectional"))
    )
    (net (code "98") (name "unconnected-(U15-P2.5{slash}TA2.2-Pad34)") (class "Default")
      (node (ref "U15") (pin "34") (pinfunction "P2.5/TA2.2_34") (pintype "bidirectional"))
    )
    (net (code "99") (name "unconnected-(U15-P2.6{slash}RTCCLK{slash}DMAE0-Pad35)") (class "Default")
      (node (ref "U15") (pin "35") (pinfunction "P2.6/RTCCLK/DMAE0_35") (pintype "bidirectional"))
    )
    (net (code "100") (name "unconnected-(U15-P2.7{slash}UCB0STE{slash}UCA0CLK-Pad36)") (class "Default")
      (node (ref "U15") (pin "36") (pinfunction "P2.7/UCB0STE/UCA0CLK_36") (pintype "bidirectional"))
    )
    (net (code "101") (name "unconnected-(U15-P3.5{slash}TB0.5-Pad42)") (class "Default")
      (node (ref "U15") (pin "42") (pinfunction "P3.5/TB0.5_42") (pintype "bidirectional"))
    )
    (net (code "102") (name "unconnected-(U15-P3.6{slash}TB0.6-Pad43)") (class "Default")
      (node (ref "U15") (pin "43") (pinfunction "P3.6/TB0.6_43") (pintype "bidirectional"))
    )
    (net (code "103") (name "unconnected-(U15-P3.7{slash}TB0OUTH{slash}SVMOUT-Pad44)") (class "Default")
      (node (ref "U15") (pin "44") (pinfunction "P3.7/TB0OUTH/SVMOUT_44") (pintype "bidirectional"))
    )
    (net (code "104") (name "unconnected-(U15-P4.0{slash}PM_UCB1STE{slash}PM_UCA1CLK-Pad45)") (class "Default")
      (node (ref "U15") (pin "45") (pinfunction "P4.0/PM_UCB1STE/PM_UCA1CLK_45") (pintype "bidirectional"))
    )
    (net (code "105") (name "unconnected-(U15-P4.1{slash}PM_UCB1SIMO{slash}PM_UCB1SDA-Pad46)") (class "Default")
      (node (ref "U15") (pin "46") (pinfunction "P4.1/PM_UCB1SIMO/PM_UCB1SDA_46") (pintype "bidirectional"))
    )
    (net (code "106") (name "unconnected-(U15-P4.2{slash}PM_UCB1SOMI{slash}PM_UCB1SCL-Pad47)") (class "Default")
      (node (ref "U15") (pin "47") (pinfunction "P4.2/PM_UCB1SOMI/PM_UCB1SCL_47") (pintype "bidirectional"))
    )
    (net (code "107") (name "unconnected-(U15-P4.3{slash}PM_UCB1CLK{slash}PM_UCA1STE-Pad48)") (class "Default")
      (node (ref "U15") (pin "48") (pinfunction "P4.3/PM_UCB1CLK/PM_UCA1STE_48") (pintype "bidirectional"))
    )
    (net (code "108") (name "unconnected-(U15-P5.0{slash}A8{slash}VREF+{slash}VEREF+-Pad9)") (class "Default")
      (node (ref "U15") (pin "9") (pinfunction "P5.0/A8/VREF+/VEREF+_9") (pintype "bidirectional"))
    )
    (net (code "109") (name "unconnected-(U15-P5.1{slash}A9{slash}VREF-{slash}VEREF--Pad10)") (class "Default")
      (node (ref "U15") (pin "10") (pinfunction "P5.1/A9/VREF-/VEREF-_10") (pintype "bidirectional"))
    )
    (net (code "110") (name "unconnected-(U15-P6.0{slash}CB0{slash}A0-Pad77)") (class "Default")
      (node (ref "U15") (pin "77") (pinfunction "P6.0/CB0/A0_77") (pintype "bidirectional"))
    )
    (net (code "111") (name "unconnected-(U15-P6.1{slash}CB1{slash}A1-Pad78)") (class "Default")
      (node (ref "U15") (pin "78") (pinfunction "P6.1/CB1/A1_78") (pintype "bidirectional"))
    )
    (net (code "112") (name "unconnected-(U15-P6.2{slash}CB2{slash}A2-Pad79)") (class "Default")
      (node (ref "U15") (pin "79") (pinfunction "P6.2/CB2/A2_79") (pintype "bidirectional"))
    )
    (net (code "113") (name "unconnected-(U15-P6.3{slash}CB3{slash}A3-Pad80)") (class "Default")
      (node (ref "U15") (pin "80") (pinfunction "P6.3/CB3/A3_80") (pintype "bidirectional"))
    )
    (net (code "114") (name "unconnected-(U15-P7.2{slash}CB10{slash}A14-Pad7)") (class "Default")
      (node (ref "U15") (pin "7") (pinfunction "P7.2/CB10/A14_7") (pintype "bidirectional"))
    )
    (net (code "115") (name "unconnected-(U15-P7.3{slash}CB11{slash}A15-Pad8)") (class "Default")
      (node (ref "U15") (pin "8") (pinfunction "P7.3/CB11/A15_8") (pintype "bidirectional"))
    )
    (net (code "116") (name "unconnected-(U15-P7.7{slash}TB0CLK{slash}MCLK-Pad60)") (class "Default")
      (node (ref "U15") (pin "60") (pinfunction "P7.7/TB0CLK/MCLK_60") (pintype "bidirectional"))
    )
    (net (code "117") (name "unconnected-(U15-P8.0-Pad15)") (class "Default")
      (node (ref "U15") (pin "15") (pinfunction "P8.0_15") (pintype "bidirectional"))
    )
    (net (code "118") (name "unconnected-(U15-P8.1-Pad16)") (class "Default")
      (node (ref "U15") (pin "16") (pinfunction "P8.1_16") (pintype "bidirectional"))
    )
    (net (code "119") (name "unconnected-(U15-P8.2-Pad17)") (class "Default")
      (node (ref "U15") (pin "17") (pinfunction "P8.2_17") (pintype "bidirectional"))
    )
    (net (code "120") (name "unconnected-(U15-PJ.0{slash}TDO-Pad72)") (class "Default")
      (node (ref "U15") (pin "72") (pinfunction "PJ.0/TDO_72") (pintype "bidirectional"))
    )
    (net (code "121") (name "unconnected-(U15-PJ.1{slash}TDI{slash}TCLK-Pad73)") (class "Default")
      (node (ref "U15") (pin "73") (pinfunction "PJ.1/TDI/TCLK_73") (pintype "bidirectional"))
    )
    (net (code "122") (name "unconnected-(U15-PJ.2{slash}TMS-Pad74)") (class "Default")
      (node (ref "U15") (pin "74") (pinfunction "PJ.2/TMS_74") (pintype "bidirectional"))
    )
    (net (code "123") (name "unconnected-(U15-PJ.3{slash}TCK-Pad75)") (class "Default")
      (node (ref "U15") (pin "75") (pinfunction "PJ.3/TCK_75") (pintype "bidirectional"))
    )
    (net (code "124") (name "unconnected-(U15-PU.0{slash}DP-Pad62)") (class "Default")
      (node (ref "U15") (pin "62") (pinfunction "PU.0/DP_62") (pintype "bidirectional"))
    )
    (net (code "125") (name "unconnected-(U15-PU.1{slash}DM-Pad64)") (class "Default")
      (node (ref "U15") (pin "64") (pinfunction "PU.1/DM_64") (pintype "bidirectional"))
    )
    (net (code "126") (name "unconnected-(U15-V1.8-Pad67)") (class "Default")
      (node (ref "U15") (pin "67") (pinfunction "V1.8_67") (pintype "bidirectional"))
    )
    (net (code "127") (name "unconnected-(U15-VUSB-Pad66)") (class "Default")
      (node (ref "U15") (pin "66") (pinfunction "VUSB_66") (pintype "bidirectional"))
    )
    (net (code "128") (name "~{ADCS-3V3-FAULT}") (class "Default")
      (node (ref "R40") (pin "1") (pinfunction "1_1") (pintype "passive"))
      (node (ref "U$21") (pin "6") (pinfunction "6_6") (pintype "bidirectional"))
      (node (ref "U15") (pin "24") (pinfunction "P1.3/TA0.2_24") (pintype "bidirectional"))
      (node (ref "U5") (pin "8") (pinfunction "~{FAULT}_8") (pintype "open_collector"))
    )
    (net (code "129") (name "~{ADCS-5V-FAULT}") (class "Default")
      (node (ref "R34") (pin "2") (pinfunction "2_2") (pintype "passive"))
      (node (ref "R8") (pin "1") (pinfunction "1_1") (pintype "passive"))
      (node (ref "U$21") (pin "15") (pinfunction "15_15") (pintype "bidirectional"))
      (node (ref "U15") (pin "23") (pinfunction "P1.2/TA0.1_23") (pintype "bidirectional"))
    )
    (net (code "130") (name "~{GPS-3V3-FAULT}") (class "Default")
      (node (ref "R48") (pin "1") (pinfunction "1_1") (pintype "passive"))
      (node (ref "U$21") (pin "18") (pinfunction "18_18") (pintype "bidirectional"))
      (node (ref "U14") (pin "8") (pinfunction "~{FAULT}_8") (pintype "open_collector"))
      (node (ref "U15") (pin "25") (pinfunction "P1.4/TA0.3_25") (pintype "bidirectional"))
    )
    (net (code "131") (name "~{OBC-3V3-FAULT}") (class "Default")
      (node (ref "R11") (pin "1") (pinfunction "1_1") (pintype "passive"))
      (node (ref "U$21") (pin "3") (pinfunction "3_3") (pintype "bidirectional"))
      (node (ref "U15") (pin "22") (pinfunction "P1.1/TA0.0_22") (pintype "bidirectional"))
      (node (ref "U3") (pin "8") (pinfunction "~{FAULT}_8") (pintype "open_collector"))
    )
    (net (code "132") (name "~{OBC-5V-FAULT}") (class "Default")
      (node (ref "R2") (pin "1") (pinfunction "1_1") (pintype "passive"))
      (node (ref "R3") (pin "2") (pinfunction "2_2") (pintype "passive"))
      (node (ref "U$21") (pin "12") (pinfunction "12_12") (pintype "bidirectional"))
      (node (ref "U15") (pin "21") (pinfunction "P1.0/TA0CLK/ACLK_21") (pintype "bidirectional"))
    )
    (net (code "133") (name "~{RF-3V3-FAULT}") (class "Default")
      (node (ref "R46") (pin "1") (pinfunction "1_1") (pintype "passive"))
      (node (ref "U$21") (pin "9") (pinfunction "9_9") (pintype "bidirectional"))
      (node (ref "U15") (pin "26") (pinfunction "P1.5/TA0.4_26") (pintype "bidirectional"))
      (node (ref "U17") (pin "8") (pinfunction "~{FAULT}_8") (pintype "open_collector"))
    )
  )
)
